# io-board-f-2.net
KiCad netlist of a schematic drawn in EAGLE
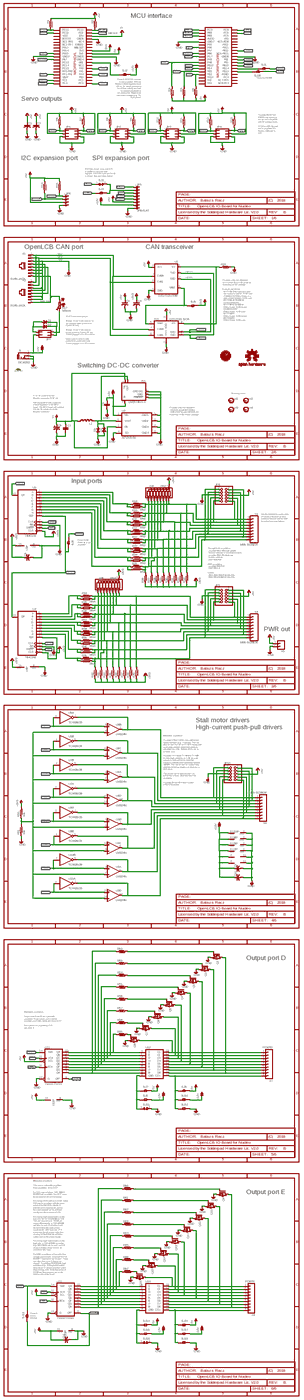
[diagram p0: schematic, sheet 1, overview]
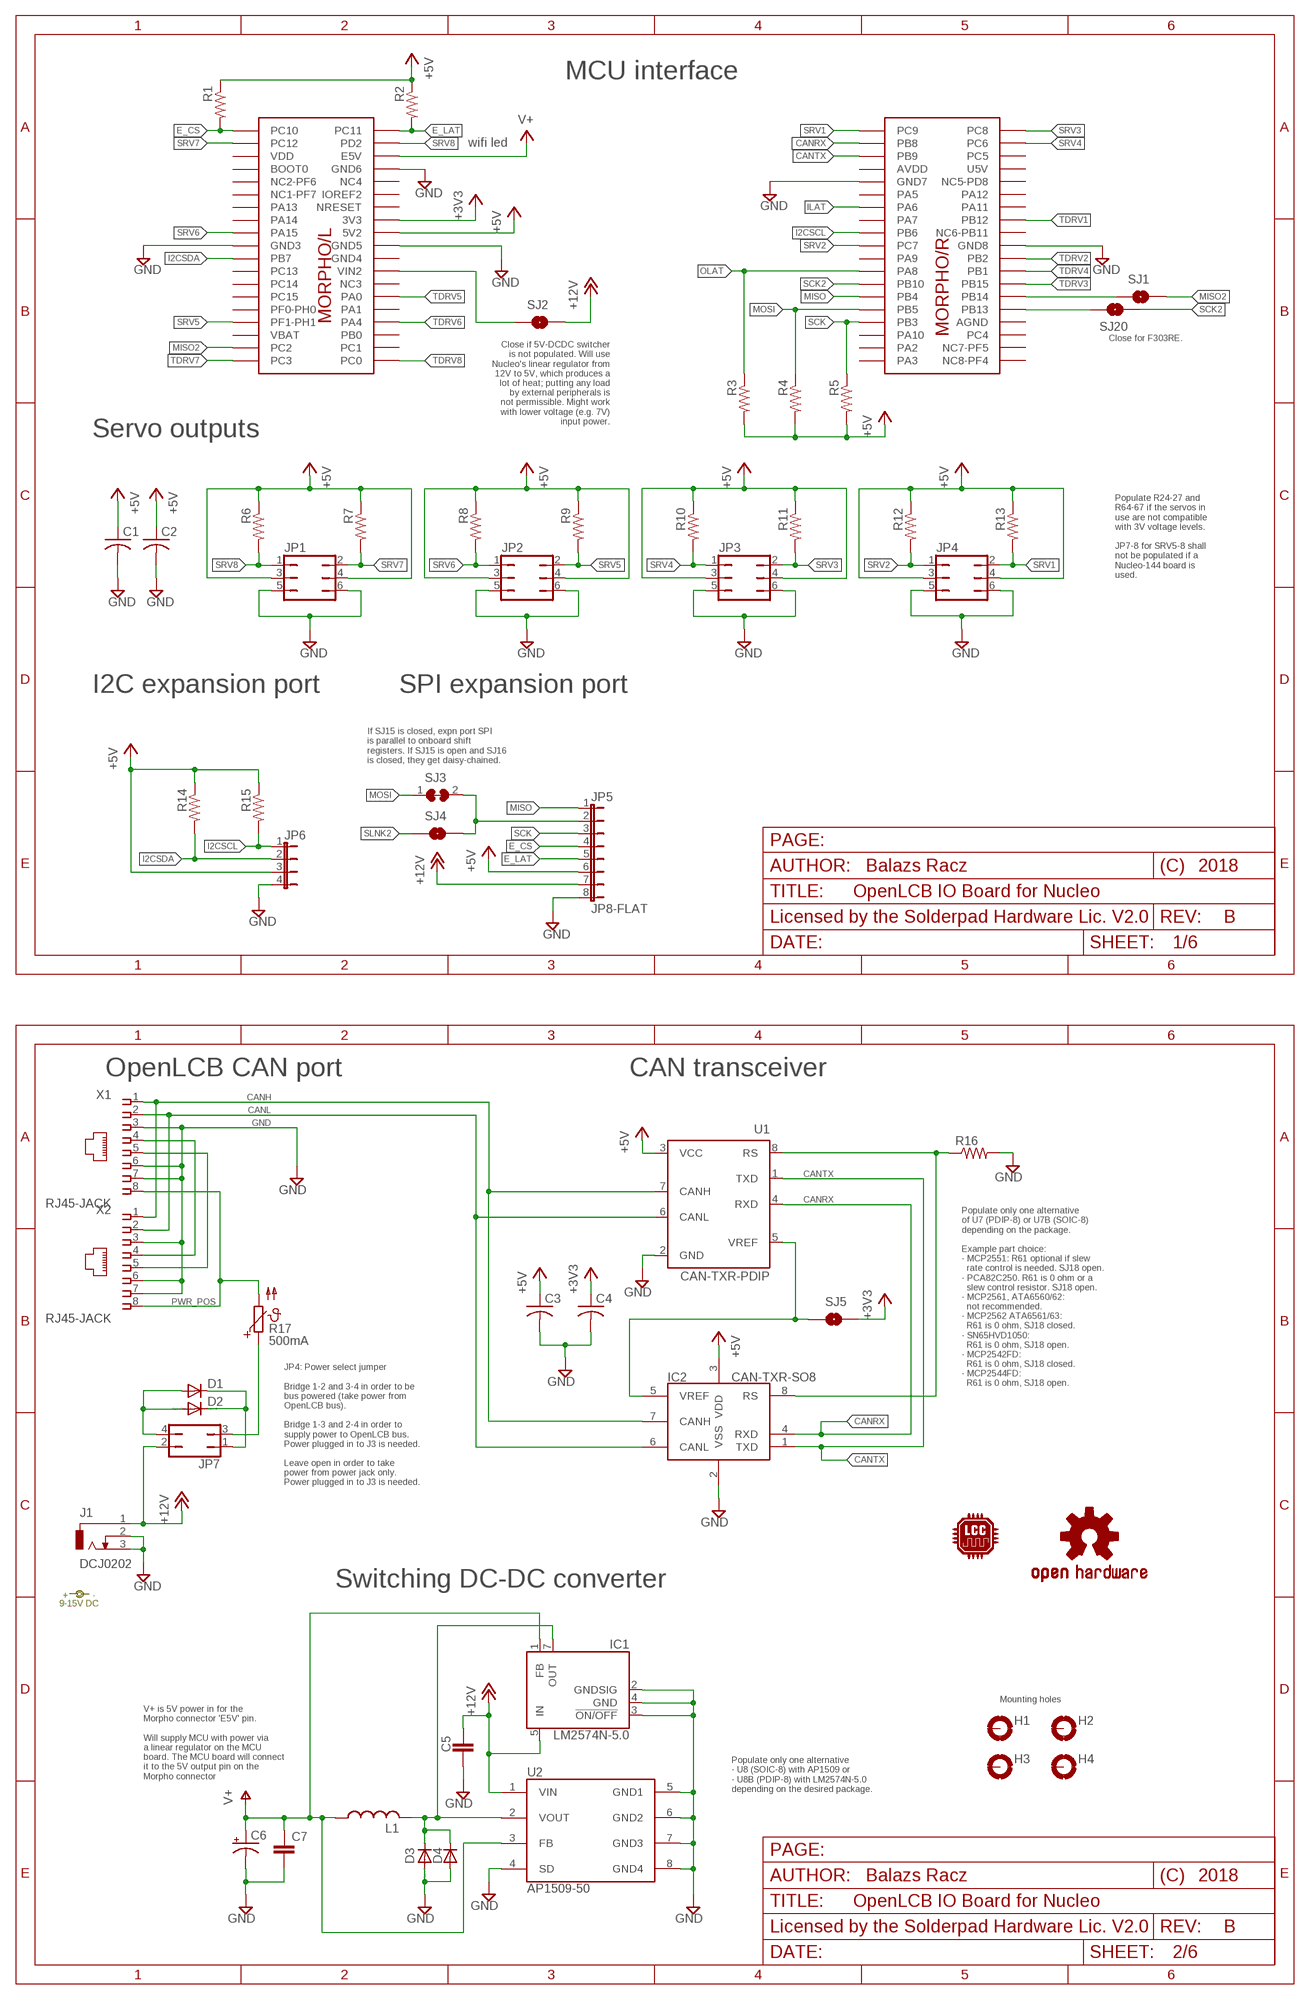
[diagram p1: schematic, sheet 1, part 1 of 4]
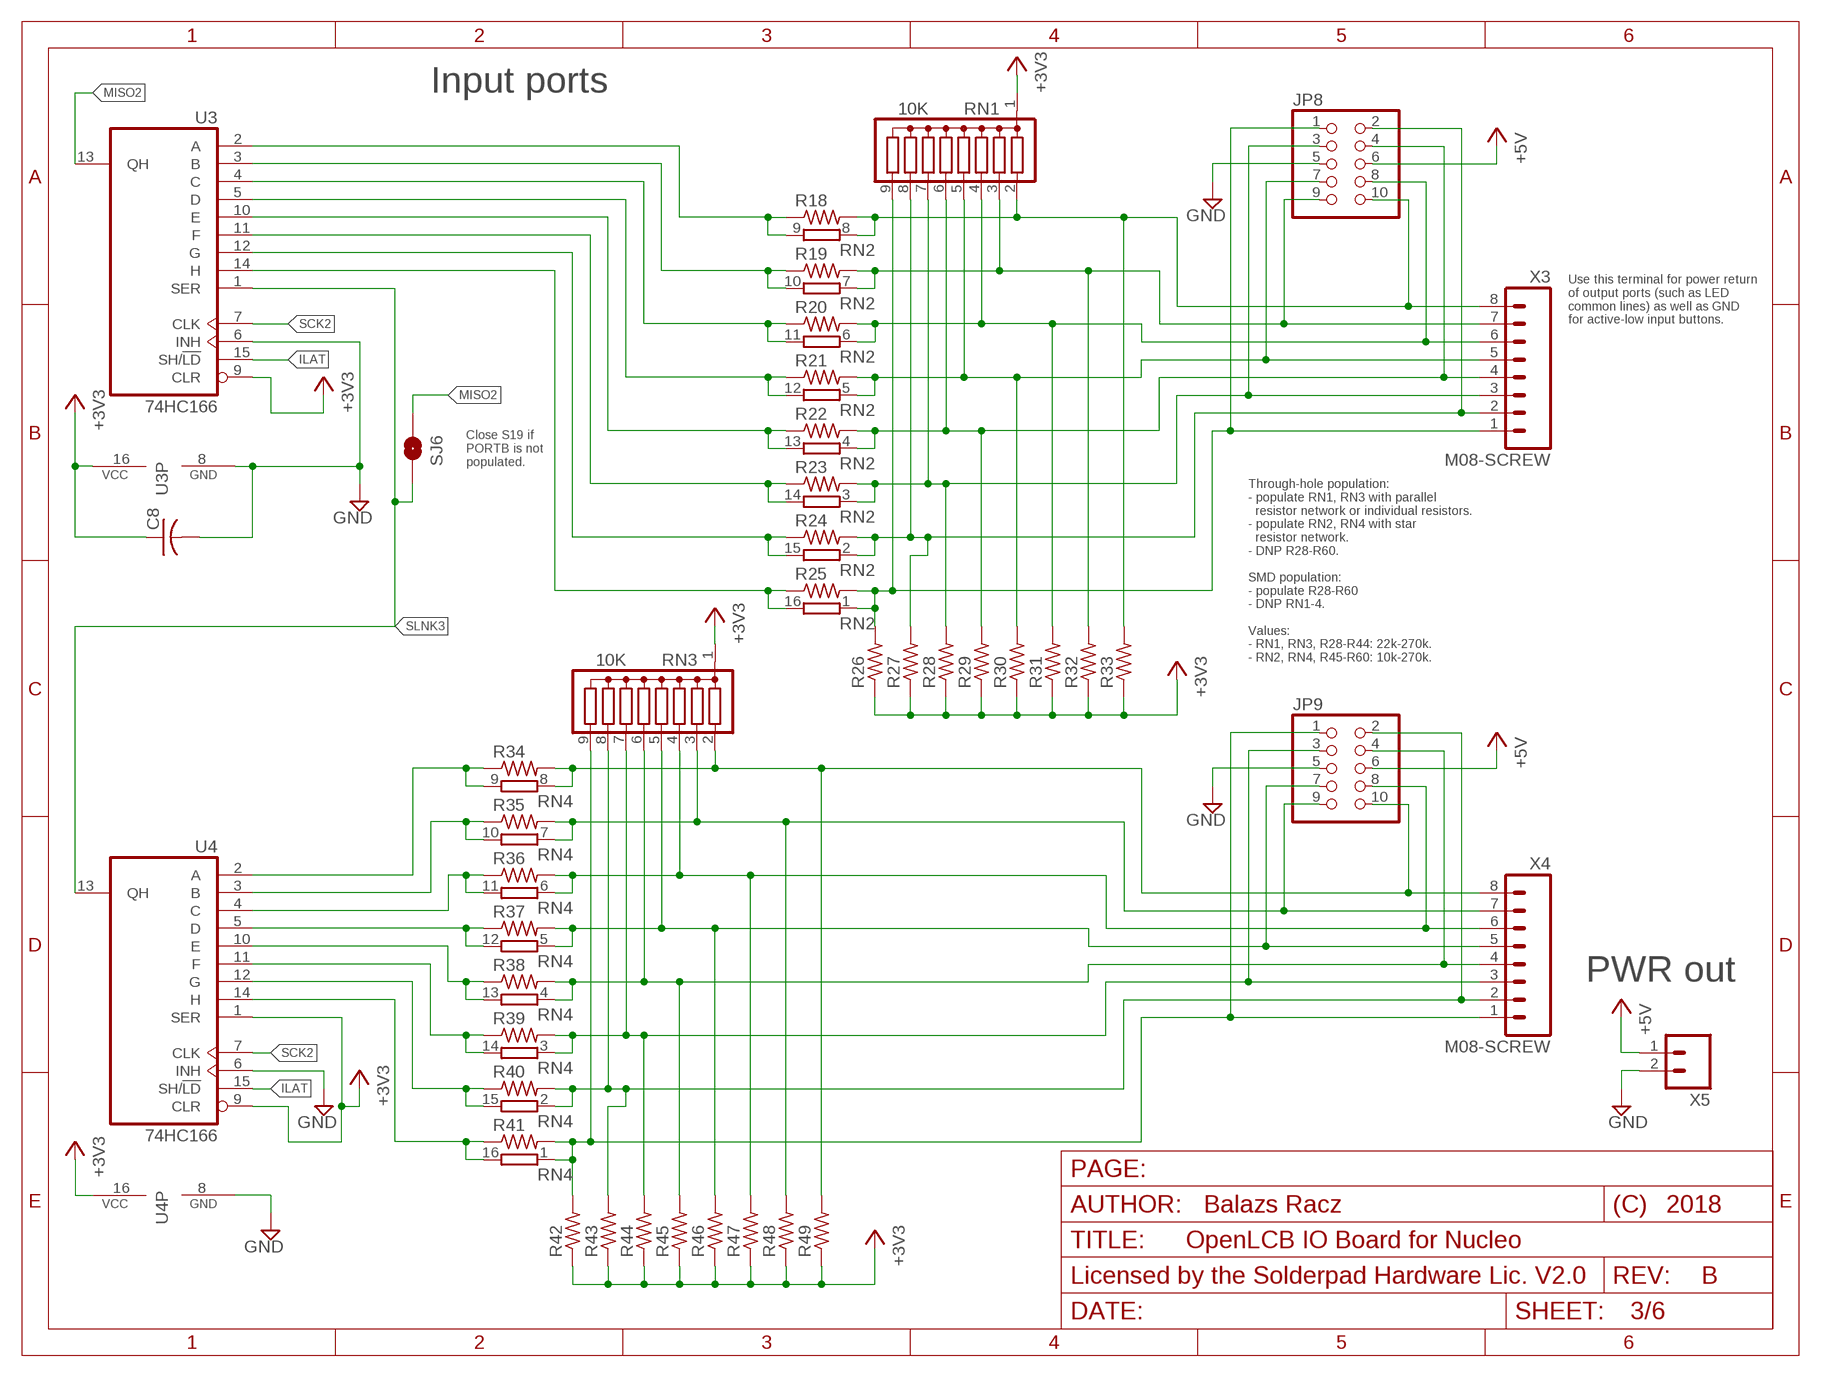
[diagram p2: schematic, sheet 1, part 2 of 4]
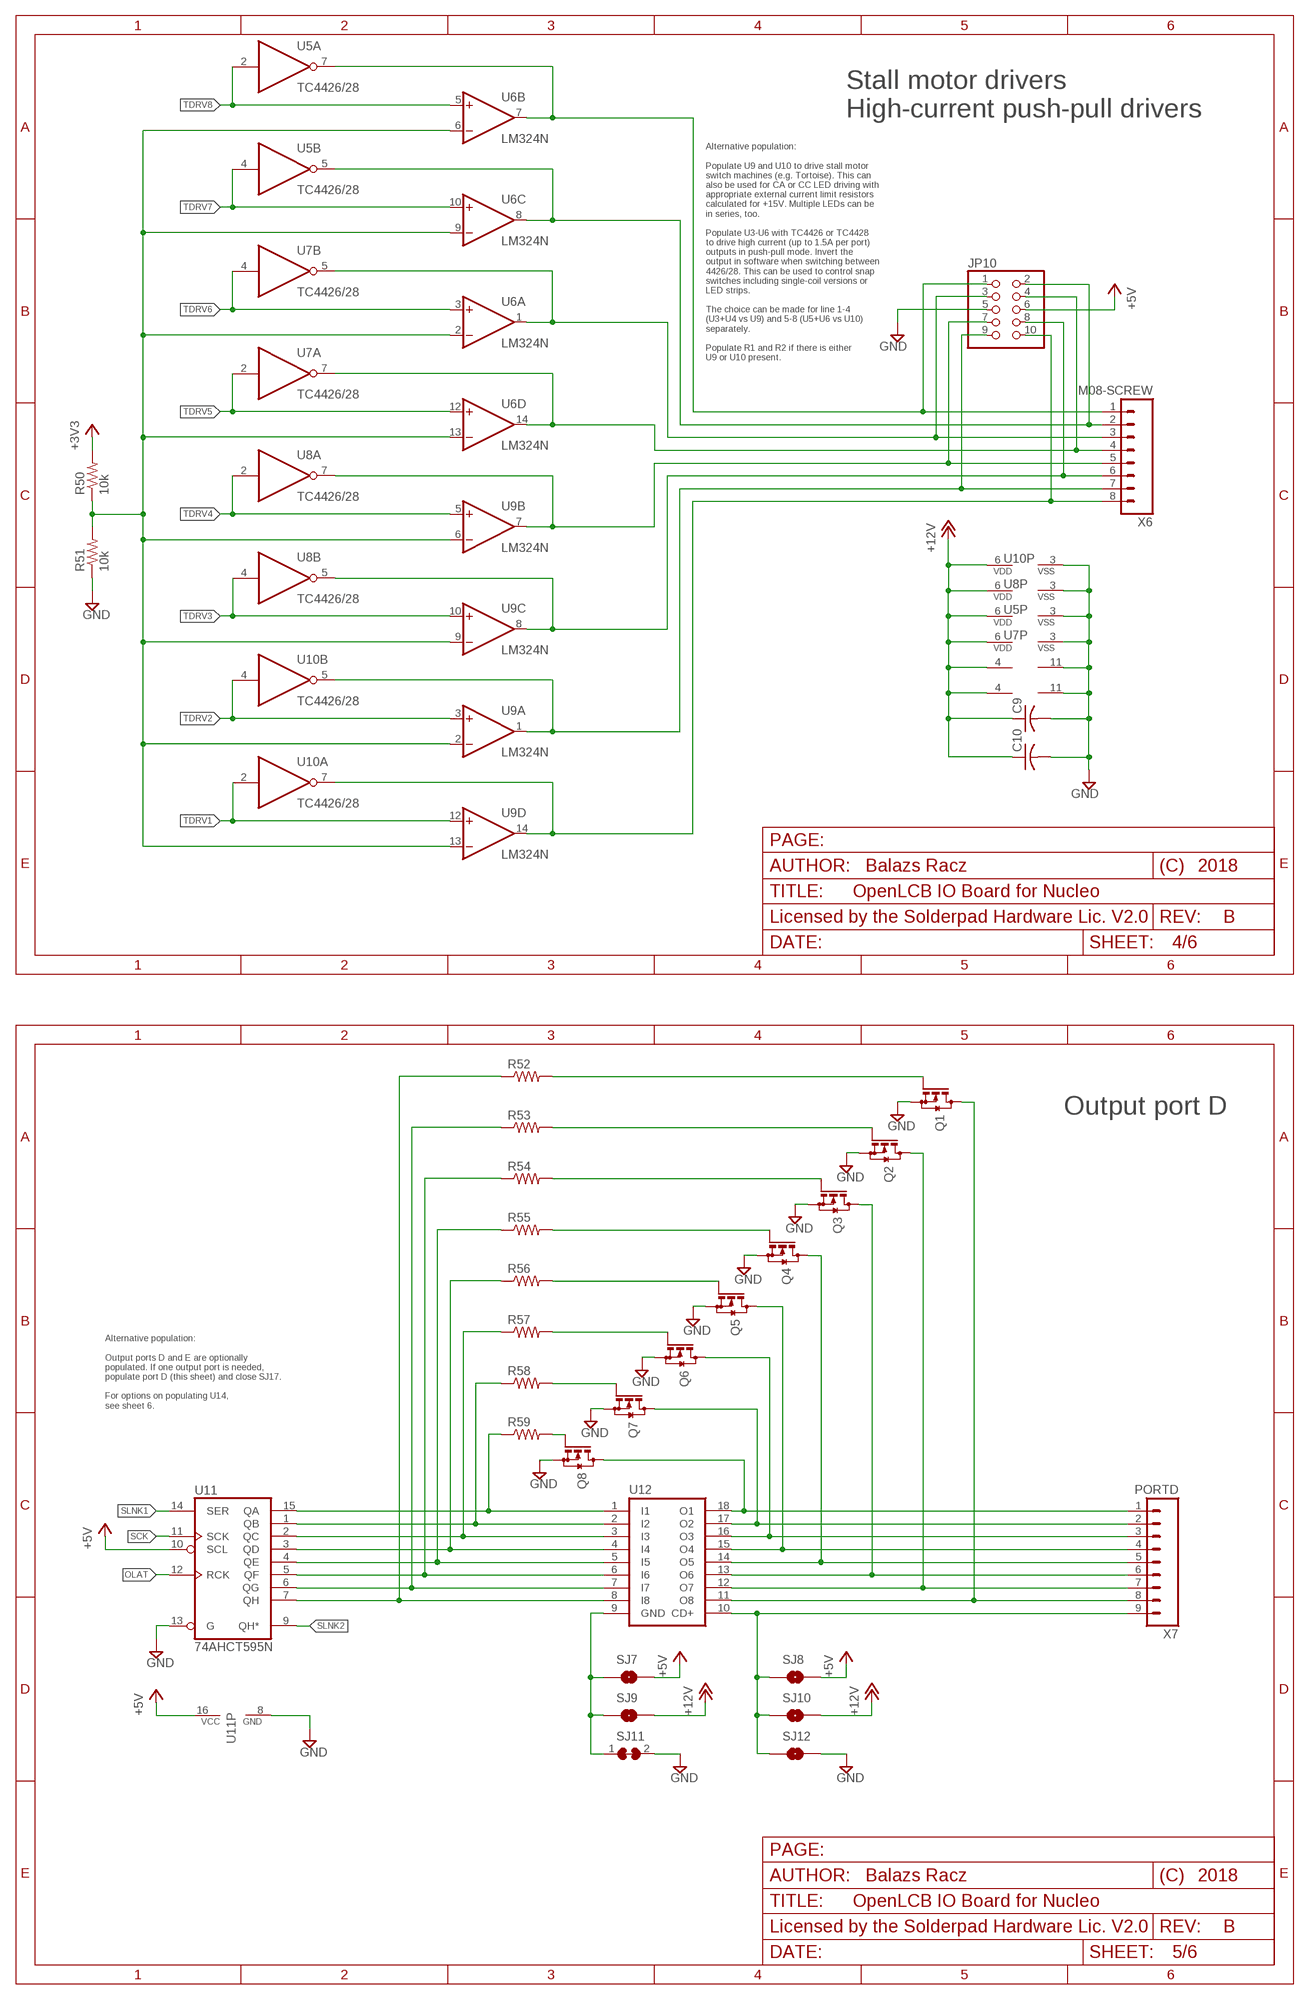
[diagram p3: schematic, sheet 1, part 3 of 4]
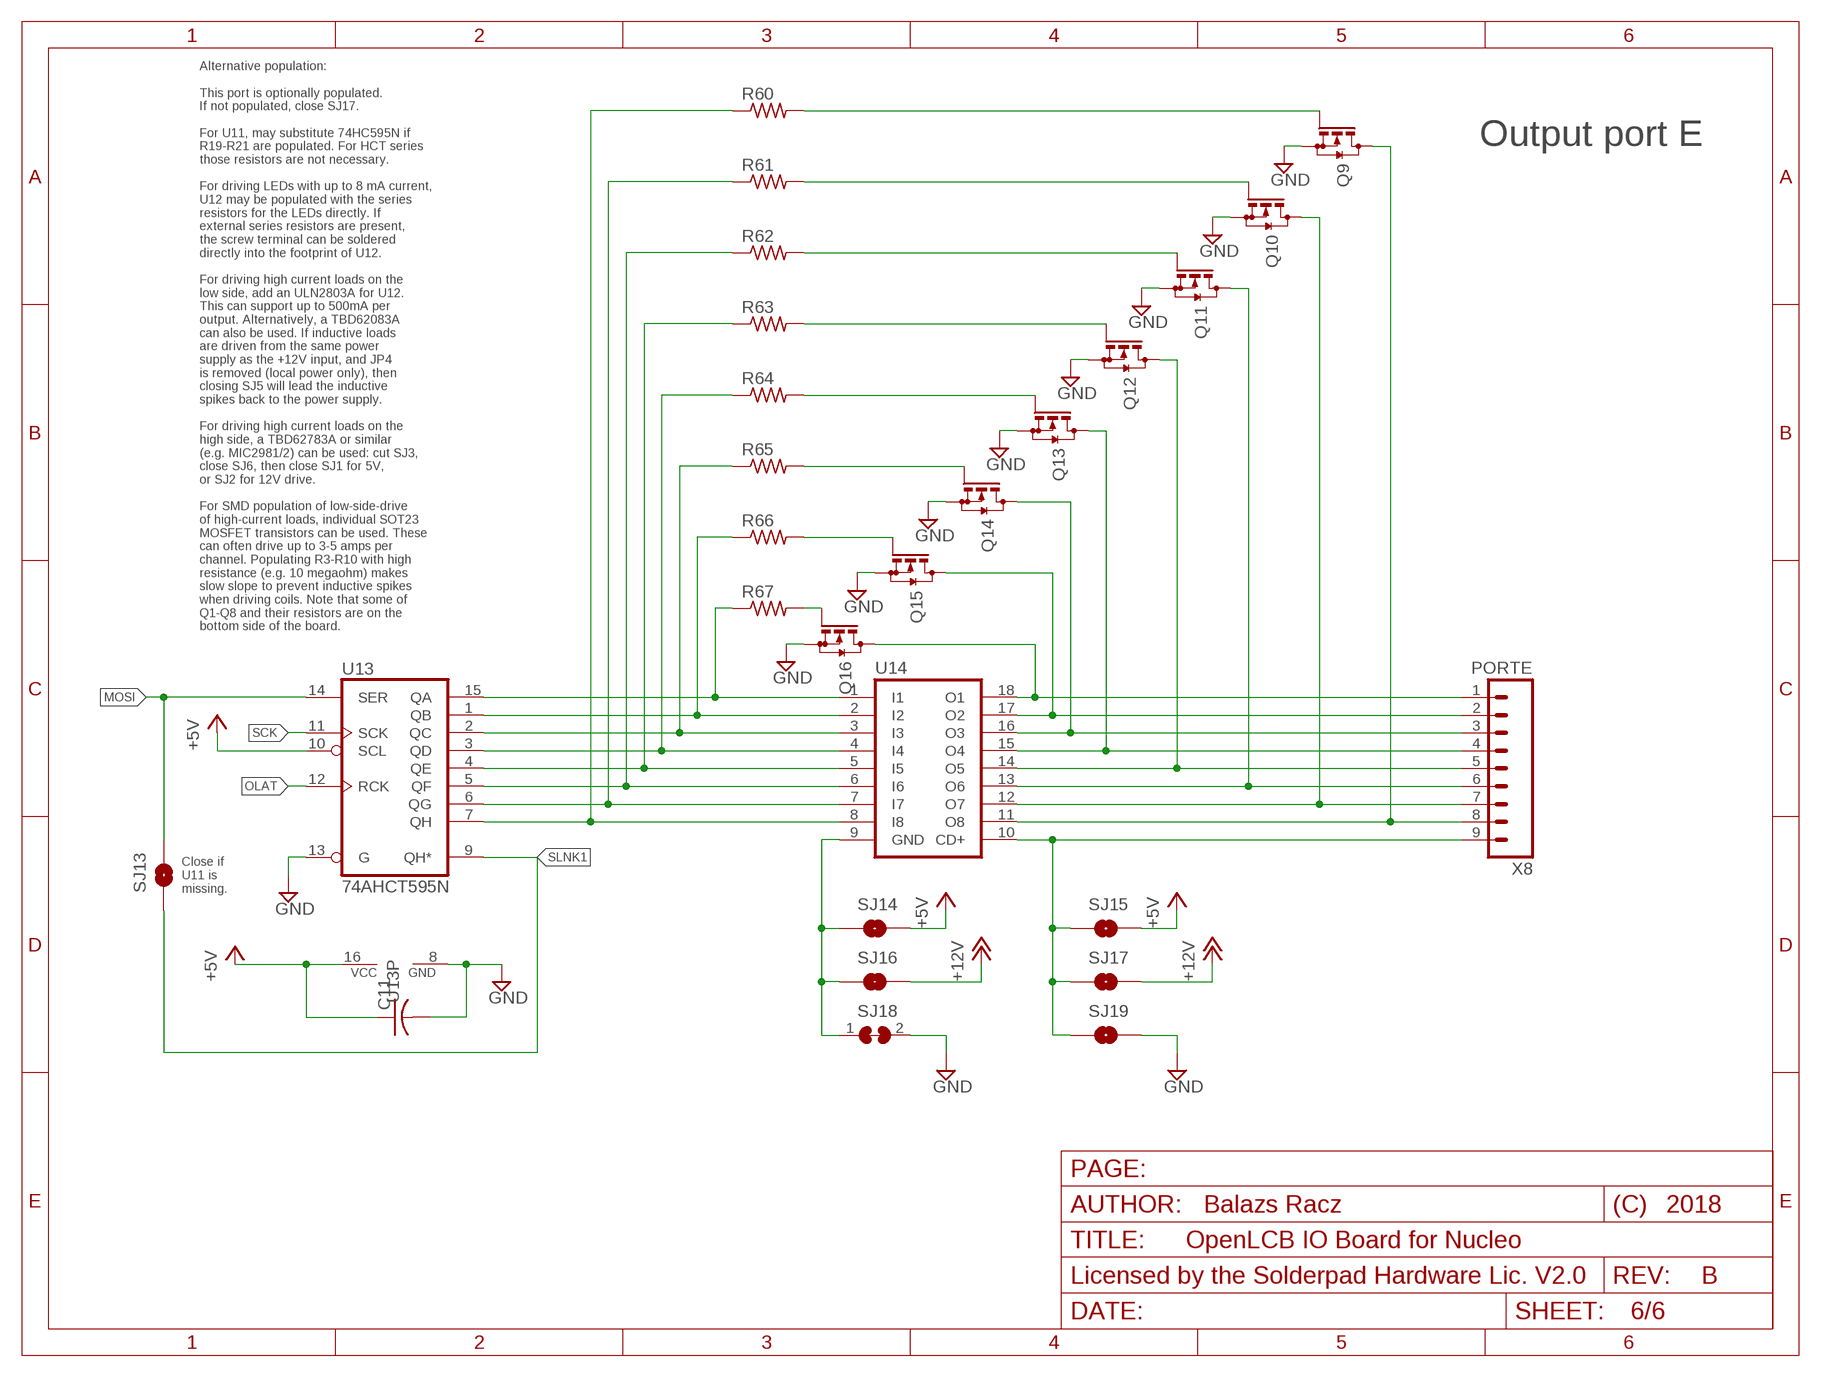
[diagram p4: schematic, sheet 1, part 4 of 4]

(export (version "E")
  (design (tool "Eeschema 10.0.6"))
  (components
    (comp (ref "C1")
      (value "C-USC1206")
      (footprint "eagle-import:C1206")
      (libsource (lib "eagle-import") (part "C-USC1206"))
    )
    (comp (ref "C2")
      (value "C-USC1206")
      (footprint "eagle-import:C1206")
      (libsource (lib "eagle-import") (part "C-USC1206"))
    )
    (comp (ref "C3")
      (value "C-USC0805")
      (footprint "eagle-import:C0805")
      (libsource (lib "eagle-import") (part "C-USC0805"))
    )
    (comp (ref "C4")
      (value "C-USC0805")
      (footprint "eagle-import:C0805")
      (libsource (lib "eagle-import") (part "C-USC0805"))
    )
    (comp (ref "C5")
      (value "C-EUC1206")
      (footprint "eagle-import:C1206")
      (libsource (lib "eagle-import") (part "C-EUC1206"))
    )
    (comp (ref "C6")
      (value "CPOL-USE2.5-5")
      (footprint "eagle-import:E2,5-5")
      (libsource (lib "eagle-import") (part "CPOL-USE2.5-5"))
    )
    (comp (ref "C7")
      (value "C-EUC1206")
      (footprint "eagle-import:C1206")
      (libsource (lib "eagle-import") (part "C-EUC1206"))
    )
    (comp (ref "C8")
      (value "C-USC0805")
      (footprint "eagle-import:C0805")
      (libsource (lib "eagle-import") (part "C-USC0805"))
    )
    (comp (ref "C9")
      (value "C-USC1206")
      (footprint "eagle-import:C1206")
      (libsource (lib "eagle-import") (part "C-USC1206"))
    )
    (comp (ref "C10")
      (value "C-USC1206")
      (footprint "eagle-import:C1206")
      (libsource (lib "eagle-import") (part "C-USC1206"))
    )
    (comp (ref "C11")
      (value "C-USC0805")
      (footprint "eagle-import:C0805")
      (libsource (lib "eagle-import") (part "C-USC0805"))
    )
    (comp (ref "D1")
      (value "DIODEDO-214AA-NODOC")
      (footprint "eagle-import:DO214AA-NODOC")
      (libsource (lib "eagle-import") (part "DIODEDO-214AA-NODOC"))
    )
    (comp (ref "D2")
      (value "DIODE-DO41-7.6")
      (footprint "eagle-import:DO41-7.6")
      (libsource (lib "eagle-import") (part "DIODE-DO41-7.6"))
    )
    (comp (ref "D3")
      (value "DIODE-DO41-7.6")
      (footprint "eagle-import:DO41-7.6")
      (libsource (lib "eagle-import") (part "DIODE-DO41-7.6"))
    )
    (comp (ref "D4")
      (value "DIODEDO-214AA-NODOC")
      (footprint "eagle-import:DO214AA-NODOC")
      (libsource (lib "eagle-import") (part "DIODEDO-214AA-NODOC"))
    )
    (comp (ref "G1")
      (value "NUCLEO_64_GENERIC")
      (footprint "eagle-import:NUCLEO_BRD_BASE64")
      (libsource (lib "eagle-import") (part "NUCLEO_64_GENERIC"))
    )
    (comp (ref "H1")
      (value "MOUNT-PAD-ROUND3.3")
      (footprint "eagle-import:3,3-PAD")
      (libsource (lib "eagle-import") (part "MOUNT-PAD-ROUND3.3"))
    )
    (comp (ref "H2")
      (value "MOUNT-PAD-ROUND3.3")
      (footprint "eagle-import:3,3-PAD")
      (libsource (lib "eagle-import") (part "MOUNT-PAD-ROUND3.3"))
    )
    (comp (ref "H3")
      (value "MOUNT-PAD-ROUND3.3")
      (footprint "eagle-import:3,3-PAD")
      (libsource (lib "eagle-import") (part "MOUNT-PAD-ROUND3.3"))
    )
    (comp (ref "H4")
      (value "MOUNT-PAD-ROUND3.3")
      (footprint "eagle-import:3,3-PAD")
      (libsource (lib "eagle-import") (part "MOUNT-PAD-ROUND3.3"))
    )
    (comp (ref "IC1")
      (value "LM2574N-5.0")
      (footprint "eagle-import:DIL08")
      (libsource (lib "eagle-import") (part "LM2574?-N5.0"))
    )
    (comp (ref "IC2")
      (value "CAN-TXR-SO8")
      (footprint "eagle-import:SO-08")
      (libsource (lib "eagle-import") (part "MCP2551-SN"))
    )
    (comp (ref "J1")
      (value "DCJ0202")
      (footprint "eagle-import:DCJ0202")
      (libsource (lib "eagle-import") (part "DCJ0202"))
    )
    (comp (ref "JP1")
      (value "JP3Q")
      (footprint "eagle-import:JP3Q")
      (libsource (lib "eagle-import") (part "JP3Q"))
    )
    (comp (ref "JP2")
      (value "JP3Q")
      (footprint "eagle-import:JP3Q")
      (libsource (lib "eagle-import") (part "JP3Q"))
    )
    (comp (ref "JP3")
      (value "JP3Q")
      (footprint "eagle-import:JP3Q")
      (libsource (lib "eagle-import") (part "JP3Q"))
    )
    (comp (ref "JP4")
      (value "JP3Q")
      (footprint "eagle-import:JP3Q")
      (libsource (lib "eagle-import") (part "JP3Q"))
    )
    (comp (ref "JP5")
      (value "JP8-FLAT")
      (footprint "eagle-import:JP8F")
      (libsource (lib "eagle-import") (part "JP8-FLAT"))
    )
    (comp (ref "JP6")
      (value "JP4-FLAT")
      (footprint "eagle-import:JP4F")
      (libsource (lib "eagle-import") (part "JP4-FLAT"))
    )
    (comp (ref "JP7")
      (value "JP2Q")
      (footprint "eagle-import:JP2Q")
      (libsource (lib "eagle-import") (part "JP2Q"))
    )
    (comp (ref "JP8")
      (value "PINHD-2X5CN")
      (footprint "eagle-import:CON10M")
      (libsource (lib "eagle-import") (part "PINHD-2X5CN"))
    )
    (comp (ref "JP9")
      (value "PINHD-2X5CN")
      (footprint "eagle-import:CON10M")
      (libsource (lib "eagle-import") (part "PINHD-2X5CN"))
    )
    (comp (ref "JP10")
      (value "PINHD-2X5CN")
      (footprint "eagle-import:CON10M")
      (libsource (lib "eagle-import") (part "PINHD-2X5CN"))
    )
    (comp (ref "L1")
      (value "L-US")
      (footprint "eagle-import:L5-8,5")
      (libsource (lib "eagle-import") (part "L-US"))
    )
    (comp (ref "LG1")
      (value "LCC_LOGO")
      (footprint "eagle-import:LCC_LOGO")
      (libsource (lib "eagle-import") (part "LCC_LOGO"))
    )
    (comp (ref "LOGO1")
      (value "DOC-OSHW-LOGOM")
      (footprint "eagle-import:OSHW-LOGO-M")
      (libsource (lib "eagle-import") (part "DOC-OSHW-LOGOM"))
    )
    (comp (ref "P1")
      (value "9-15V DC")
      (footprint "eagle-import:POWER_USAGE")
      (libsource (lib "eagle-import") (part "DOC-POWER_LABEL"))
    )
    (comp (ref "Q1")
      (value "BSS123")
      (footprint "eagle-import:SOT23")
      (libsource (lib "eagle-import") (part "BSS123"))
    )
    (comp (ref "Q2")
      (value "BSS123")
      (footprint "eagle-import:SOT23")
      (libsource (lib "eagle-import") (part "BSS123"))
    )
    (comp (ref "Q3")
      (value "BSS123")
      (footprint "eagle-import:SOT23")
      (libsource (lib "eagle-import") (part "BSS123"))
    )
    (comp (ref "Q4")
      (value "BSS123")
      (footprint "eagle-import:SOT23")
      (libsource (lib "eagle-import") (part "BSS123"))
    )
    (comp (ref "Q5")
      (value "BSS123")
      (footprint "eagle-import:SOT23")
      (libsource (lib "eagle-import") (part "BSS123"))
    )
    (comp (ref "Q6")
      (value "BSS123")
      (footprint "eagle-import:SOT23")
      (libsource (lib "eagle-import") (part "BSS123"))
    )
    (comp (ref "Q7")
      (value "BSS123")
      (footprint "eagle-import:SOT23")
      (libsource (lib "eagle-import") (part "BSS123"))
    )
    (comp (ref "Q8")
      (value "BSS123")
      (footprint "eagle-import:SOT23")
      (libsource (lib "eagle-import") (part "BSS123"))
    )
    (comp (ref "Q9")
      (value "BSS123")
      (footprint "eagle-import:SOT23")
      (libsource (lib "eagle-import") (part "BSS123"))
    )
    (comp (ref "Q10")
      (value "BSS123")
      (footprint "eagle-import:SOT23")
      (libsource (lib "eagle-import") (part "BSS123"))
    )
    (comp (ref "Q11")
      (value "BSS123")
      (footprint "eagle-import:SOT23")
      (libsource (lib "eagle-import") (part "BSS123"))
    )
    (comp (ref "Q12")
      (value "BSS123")
      (footprint "eagle-import:SOT23")
      (libsource (lib "eagle-import") (part "BSS123"))
    )
    (comp (ref "Q13")
      (value "BSS123")
      (footprint "eagle-import:SOT23")
      (libsource (lib "eagle-import") (part "BSS123"))
    )
    (comp (ref "Q14")
      (value "BSS123")
      (footprint "eagle-import:SOT23")
      (libsource (lib "eagle-import") (part "BSS123"))
    )
    (comp (ref "Q15")
      (value "BSS123")
      (footprint "eagle-import:SOT23")
      (libsource (lib "eagle-import") (part "BSS123"))
    )
    (comp (ref "Q16")
      (value "BSS123")
      (footprint "eagle-import:SOT23")
      (libsource (lib "eagle-import") (part "BSS123"))
    )
    (comp (ref "R1")
      (value "R-US_R0805")
      (footprint "eagle-import:R0805")
      (libsource (lib "eagle-import") (part "rcl_334_R-US_R0805"))
    )
    (comp (ref "R2")
      (value "R-US_R0805")
      (footprint "eagle-import:R0805")
      (libsource (lib "eagle-import") (part "rcl_334_R-US_R0805"))
    )
    (comp (ref "R3")
      (value "R-US_R0805")
      (footprint "eagle-import:R0805")
      (libsource (lib "eagle-import") (part "rcl_334_R-US_R0805"))
    )
    (comp (ref "R4")
      (value "R-US_R0805")
      (footprint "eagle-import:R0805")
      (libsource (lib "eagle-import") (part "rcl_334_R-US_R0805"))
    )
    (comp (ref "R5")
      (value "R-US_R0805")
      (footprint "eagle-import:R0805")
      (libsource (lib "eagle-import") (part "rcl_334_R-US_R0805"))
    )
    (comp (ref "R6")
      (value "R-US_R0805")
      (footprint "eagle-import:R0805")
      (libsource (lib "eagle-import") (part "rcl_334_R-US_R0805"))
    )
    (comp (ref "R7")
      (value "R-US_R0805")
      (footprint "eagle-import:R0805")
      (libsource (lib "eagle-import") (part "rcl_334_R-US_R0805"))
    )
    (comp (ref "R8")
      (value "R-US_R0805")
      (footprint "eagle-import:R0805")
      (libsource (lib "eagle-import") (part "rcl_334_R-US_R0805"))
    )
    (comp (ref "R9")
      (value "R-US_R0805")
      (footprint "eagle-import:R0805")
      (libsource (lib "eagle-import") (part "rcl_334_R-US_R0805"))
    )
    (comp (ref "R10")
      (value "R-US_R0805")
      (footprint "eagle-import:R0805")
      (libsource (lib "eagle-import") (part "rcl_334_R-US_R0805"))
    )
    (comp (ref "R11")
      (value "R-US_R0805")
      (footprint "eagle-import:R0805")
      (libsource (lib "eagle-import") (part "rcl_334_R-US_R0805"))
    )
    (comp (ref "R12")
      (value "R-US_R0805")
      (footprint "eagle-import:R0805")
      (libsource (lib "eagle-import") (part "rcl_334_R-US_R0805"))
    )
    (comp (ref "R13")
      (value "R-US_R0805")
      (footprint "eagle-import:R0805")
      (libsource (lib "eagle-import") (part "rcl_334_R-US_R0805"))
    )
    (comp (ref "R14")
      (value "R-US_R0805")
      (footprint "eagle-import:R0805")
      (libsource (lib "eagle-import") (part "rcl_334_R-US_R0805"))
    )
    (comp (ref "R15")
      (value "R-US_R0805")
      (footprint "eagle-import:R0805")
      (libsource (lib "eagle-import") (part "rcl_334_R-US_R0805"))
    )
    (comp (ref "R16")
      (value "R-US_R0805")
      (footprint "eagle-import:R0805")
      (libsource (lib "eagle-import") (part "rcl_334_R-US_R0805"))
    )
    (comp (ref "R17")
      (value "500mA")
      (footprint "eagle-import:PTC1812")
      (libsource (lib "eagle-import") (part "PTC_1812"))
    )
    (comp (ref "R18")
      (value "R-US_R0603")
      (footprint "eagle-import:R0603")
      (libsource (lib "eagle-import") (part "rcl_334_R-US_R0603"))
    )
    (comp (ref "R19")
      (value "R-US_R0603")
      (footprint "eagle-import:R0603")
      (libsource (lib "eagle-import") (part "rcl_334_R-US_R0603"))
    )
    (comp (ref "R20")
      (value "R-US_R0603")
      (footprint "eagle-import:R0603")
      (libsource (lib "eagle-import") (part "rcl_334_R-US_R0603"))
    )
    (comp (ref "R21")
      (value "R-US_R0603")
      (footprint "eagle-import:R0603")
      (libsource (lib "eagle-import") (part "rcl_334_R-US_R0603"))
    )
    (comp (ref "R22")
      (value "R-US_R0603")
      (footprint "eagle-import:R0603")
      (libsource (lib "eagle-import") (part "rcl_334_R-US_R0603"))
    )
    (comp (ref "R23")
      (value "R-US_R0603")
      (footprint "eagle-import:R0603")
      (libsource (lib "eagle-import") (part "rcl_334_R-US_R0603"))
    )
    (comp (ref "R24")
      (value "R-US_R0603")
      (footprint "eagle-import:R0603")
      (libsource (lib "eagle-import") (part "rcl_334_R-US_R0603"))
    )
    (comp (ref "R25")
      (value "R-US_R0603")
      (footprint "eagle-import:R0603")
      (libsource (lib "eagle-import") (part "rcl_334_R-US_R0603"))
    )
    (comp (ref "R26")
      (value "R-US")
      (footprint "eagle-import:R0603")
      (libsource (lib "eagle-import") (part "R-US"))
    )
    (comp (ref "R27")
      (value "R-US")
      (footprint "eagle-import:R0603")
      (libsource (lib "eagle-import") (part "R-US"))
    )
    (comp (ref "R28")
      (value "R-US")
      (footprint "eagle-import:R0603")
      (libsource (lib "eagle-import") (part "R-US"))
    )
    (comp (ref "R29")
      (value "R-US")
      (footprint "eagle-import:R0603")
      (libsource (lib "eagle-import") (part "R-US"))
    )
    (comp (ref "R30")
      (value "R-US")
      (footprint "eagle-import:R0603")
      (libsource (lib "eagle-import") (part "R-US"))
    )
    (comp (ref "R31")
      (value "R-US")
      (footprint "eagle-import:R0603")
      (libsource (lib "eagle-import") (part "R-US"))
    )
    (comp (ref "R32")
      (value "R-US")
      (footprint "eagle-import:R0603")
      (libsource (lib "eagle-import") (part "R-US"))
    )
    (comp (ref "R33")
      (value "R-US")
      (footprint "eagle-import:R0603")
      (libsource (lib "eagle-import") (part "R-US"))
    )
    (comp (ref "R34")
      (value "R-US_R0603")
      (footprint "eagle-import:R0603")
      (libsource (lib "eagle-import") (part "rcl_334_R-US_R0603"))
    )
    (comp (ref "R35")
      (value "R-US_R0603")
      (footprint "eagle-import:R0603")
      (libsource (lib "eagle-import") (part "rcl_334_R-US_R0603"))
    )
    (comp (ref "R36")
      (value "R-US_R0603")
      (footprint "eagle-import:R0603")
      (libsource (lib "eagle-import") (part "rcl_334_R-US_R0603"))
    )
    (comp (ref "R37")
      (value "R-US_R0603")
      (footprint "eagle-import:R0603")
      (libsource (lib "eagle-import") (part "rcl_334_R-US_R0603"))
    )
    (comp (ref "R38")
      (value "R-US_R0603")
      (footprint "eagle-import:R0603")
      (libsource (lib "eagle-import") (part "rcl_334_R-US_R0603"))
    )
    (comp (ref "R39")
      (value "R-US_R0603")
      (footprint "eagle-import:R0603")
      (libsource (lib "eagle-import") (part "rcl_334_R-US_R0603"))
    )
    (comp (ref "R40")
      (value "R-US_R0603")
      (footprint "eagle-import:R0603")
      (libsource (lib "eagle-import") (part "rcl_334_R-US_R0603"))
    )
    (comp (ref "R41")
      (value "R-US_R0603")
      (footprint "eagle-import:R0603")
      (libsource (lib "eagle-import") (part "rcl_334_R-US_R0603"))
    )
    (comp (ref "R42")
      (value "R-US")
      (footprint "eagle-import:R0603")
      (libsource (lib "eagle-import") (part "R-US"))
    )
    (comp (ref "R43")
      (value "R-US")
      (footprint "eagle-import:R0603")
      (libsource (lib "eagle-import") (part "R-US"))
    )
    (comp (ref "R44")
      (value "R-US")
      (footprint "eagle-import:R0603")
      (libsource (lib "eagle-import") (part "R-US"))
    )
    (comp (ref "R45")
      (value "R-US")
      (footprint "eagle-import:R0603")
      (libsource (lib "eagle-import") (part "R-US"))
    )
    (comp (ref "R46")
      (value "R-US")
      (footprint "eagle-import:R0603")
      (libsource (lib "eagle-import") (part "R-US"))
    )
    (comp (ref "R47")
      (value "R-US")
      (footprint "eagle-import:R0603")
      (libsource (lib "eagle-import") (part "R-US"))
    )
    (comp (ref "R48")
      (value "R-US")
      (footprint "eagle-import:R0603")
      (libsource (lib "eagle-import") (part "R-US"))
    )
    (comp (ref "R49")
      (value "R-US")
      (footprint "eagle-import:R0603")
      (libsource (lib "eagle-import") (part "R-US"))
    )
    (comp (ref "R50")
      (value "10k")
      (footprint "eagle-import:R0805")
      (libsource (lib "eagle-import") (part "R-US_R0805"))
    )
    (comp (ref "R51")
      (value "10k")
      (footprint "eagle-import:R0805")
      (libsource (lib "eagle-import") (part "R-US_R0805"))
    )
    (comp (ref "R52")
      (value "R-US_R0603")
      (footprint "eagle-import:R0603")
      (libsource (lib "eagle-import") (part "R-US_R0603"))
    )
    (comp (ref "R53")
      (value "R-US_R0603")
      (footprint "eagle-import:R0603")
      (libsource (lib "eagle-import") (part "R-US_R0603"))
    )
    (comp (ref "R54")
      (value "R-US_R0603")
      (footprint "eagle-import:R0603")
      (libsource (lib "eagle-import") (part "R-US_R0603"))
    )
    (comp (ref "R55")
      (value "R-US_R0603")
      (footprint "eagle-import:R0603")
      (libsource (lib "eagle-import") (part "R-US_R0603"))
    )
    (comp (ref "R56")
      (value "R-US_R0603")
      (footprint "eagle-import:R0603")
      (libsource (lib "eagle-import") (part "R-US_R0603"))
    )
    (comp (ref "R57")
      (value "R-US_R0603")
      (footprint "eagle-import:R0603")
      (libsource (lib "eagle-import") (part "R-US_R0603"))
    )
    (comp (ref "R58")
      (value "R-US_R0603")
      (footprint "eagle-import:R0603")
      (libsource (lib "eagle-import") (part "R-US_R0603"))
    )
    (comp (ref "R59")
      (value "R-US_R0603")
      (footprint "eagle-import:R0603")
      (libsource (lib "eagle-import") (part "R-US_R0603"))
    )
    (comp (ref "R60")
      (value "R-US_R0603")
      (footprint "eagle-import:R0603")
      (libsource (lib "eagle-import") (part "R-US_R0603"))
    )
    (comp (ref "R61")
      (value "R-US_R0603")
      (footprint "eagle-import:R0603")
      (libsource (lib "eagle-import") (part "R-US_R0603"))
    )
    (comp (ref "R62")
      (value "R-US_R0603")
      (footprint "eagle-import:R0603")
      (libsource (lib "eagle-import") (part "R-US_R0603"))
    )
    (comp (ref "R63")
      (value "R-US_R0603")
      (footprint "eagle-import:R0603")
      (libsource (lib "eagle-import") (part "R-US_R0603"))
    )
    (comp (ref "R64")
      (value "R-US_R0603")
      (footprint "eagle-import:R0603")
      (libsource (lib "eagle-import") (part "R-US_R0603"))
    )
    (comp (ref "R65")
      (value "R-US_R0603")
      (footprint "eagle-import:R0603")
      (libsource (lib "eagle-import") (part "R-US_R0603"))
    )
    (comp (ref "R66")
      (value "R-US_R0603")
      (footprint "eagle-import:R0603")
      (libsource (lib "eagle-import") (part "R-US_R0603"))
    )
    (comp (ref "R67")
      (value "R-US_R0603")
      (footprint "eagle-import:R0603")
      (libsource (lib "eagle-import") (part "R-US_R0603"))
    )
    (comp (ref "RN1")
      (value "10K")
      (footprint "eagle-import:SIL9")
      (libsource (lib "eagle-import") (part "G08R"))
    )
    (comp (ref "RN2")
      (value "8R-P")
      (footprint "eagle-import:DIL16")
      (libsource (lib "eagle-import") (part "8R-P"))
    )
    (comp (ref "RN3")
      (value "10K")
      (footprint "eagle-import:SIL9")
      (libsource (lib "eagle-import") (part "G08R"))
    )
    (comp (ref "RN4")
      (value "8R-P")
      (footprint "eagle-import:DIL16")
      (libsource (lib "eagle-import") (part "8R-P"))
    )
    (comp (ref "SJ1")
      (value "SJRND2")
      (footprint "eagle-import:SJ_RND2")
      (libsource (lib "eagle-import") (part "SJRND2"))
    )
    (comp (ref "SJ2")
      (value "SJRND2")
      (footprint "eagle-import:SJ_RND2")
      (libsource (lib "eagle-import") (part "SJRND2"))
    )
    (comp (ref "SJ3")
      (value "SJ-C")
      (footprint "eagle-import:SJW-C")
      (libsource (lib "eagle-import") (part "SJ-C"))
    )
    (comp (ref "SJ4")
      (value "SJRND2")
      (footprint "eagle-import:SJ_RND2")
      (libsource (lib "eagle-import") (part "SJRND2"))
    )
    (comp (ref "SJ5")
      (value "SJRND2")
      (footprint "eagle-import:SJ_RND2")
      (libsource (lib "eagle-import") (part "SJRND2"))
    )
    (comp (ref "SJ6")
      (value "SJRND2")
      (footprint "eagle-import:SJ_RND2")
      (libsource (lib "eagle-import") (part "SJRND2"))
    )
    (comp (ref "SJ7")
      (value "SJRND2")
      (footprint "eagle-import:SJ_RND2")
      (libsource (lib "eagle-import") (part "SJRND2"))
    )
    (comp (ref "SJ8")
      (value "SJRND2")
      (footprint "eagle-import:SJ_RND2")
      (libsource (lib "eagle-import") (part "SJRND2"))
    )
    (comp (ref "SJ9")
      (value "SJRND2")
      (footprint "eagle-import:SJ_RND2")
      (libsource (lib "eagle-import") (part "SJRND2"))
    )
    (comp (ref "SJ10")
      (value "SJRND2")
      (footprint "eagle-import:SJ_RND2")
      (libsource (lib "eagle-import") (part "SJRND2"))
    )
    (comp (ref "SJ11")
      (value "SJ-C")
      (footprint "eagle-import:SJW-C")
      (libsource (lib "eagle-import") (part "SJ-C"))
    )
    (comp (ref "SJ12")
      (value "SJRND2")
      (footprint "eagle-import:SJ_RND2")
      (libsource (lib "eagle-import") (part "SJRND2"))
    )
    (comp (ref "SJ13")
      (value "SJRND2")
      (footprint "eagle-import:SJ_RND2")
      (libsource (lib "eagle-import") (part "SJRND2"))
    )
    (comp (ref "SJ14")
      (value "SJRND2")
      (footprint "eagle-import:SJ_RND2")
      (libsource (lib "eagle-import") (part "SJRND2"))
    )
    (comp (ref "SJ15")
      (value "SJRND2")
      (footprint "eagle-import:SJ_RND2")
      (libsource (lib "eagle-import") (part "SJRND2"))
    )
    (comp (ref "SJ16")
      (value "SJRND2")
      (footprint "eagle-import:SJ_RND2")
      (libsource (lib "eagle-import") (part "SJRND2"))
    )
    (comp (ref "SJ17")
      (value "SJRND2")
      (footprint "eagle-import:SJ_RND2")
      (libsource (lib "eagle-import") (part "SJRND2"))
    )
    (comp (ref "SJ18")
      (value "SJ-C")
      (footprint "eagle-import:SJW-C")
      (libsource (lib "eagle-import") (part "SJ-C"))
    )
    (comp (ref "SJ19")
      (value "SJRND2")
      (footprint "eagle-import:SJ_RND2")
      (libsource (lib "eagle-import") (part "SJRND2"))
    )
    (comp (ref "SJ20")
      (value "SJRND2")
      (footprint "eagle-import:SJ_RND2")
      (libsource (lib "eagle-import") (part "SJRND2"))
    )
    (comp (ref "U1")
      (value "CAN-TXR-PDIP")
      (footprint "eagle-import:DIL08")
      (libsource (lib "eagle-import") (part "PCA82C250"))
    )
    (comp (ref "U2")
      (value "AP1509-50")
      (footprint "eagle-import:SO-08")
      (libsource (lib "eagle-import") (part "AP1509"))
    )
    (comp (ref "U3")
      (value "74HC166")
      (footprint "eagle-import:DIL16")
      (libsource (lib "eagle-import") (part "74166N"))
    )
    (comp (ref "U4")
      (value "74HC166")
      (footprint "eagle-import:DIL16")
      (libsource (lib "eagle-import") (part "74166N"))
    )
    (comp (ref "U5")
      (value "TC4426/28")
      (footprint "eagle-import:DIL08-LONG")
      (libsource (lib "eagle-import") (part "TC4426APDIP"))
    )
    (comp (ref "U6")
      (value "LM324N")
      (footprint "eagle-import:DIL14")
      (libsource (lib "eagle-import") (part "LM324N"))
    )
    (comp (ref "U7")
      (value "TC4426/28")
      (footprint "eagle-import:DIL08-LONG")
      (libsource (lib "eagle-import") (part "TC4426APDIP"))
    )
    (comp (ref "U8")
      (value "TC4426/28")
      (footprint "eagle-import:DIL08-LONG")
      (libsource (lib "eagle-import") (part "TC4426APDIP"))
    )
    (comp (ref "U9")
      (value "LM324N")
      (footprint "eagle-import:DIL14")
      (libsource (lib "eagle-import") (part "LM324N"))
    )
    (comp (ref "U10")
      (value "TC4426/28")
      (footprint "eagle-import:DIL08-LONG")
      (libsource (lib "eagle-import") (part "TC4426APDIP"))
    )
    (comp (ref "U11")
      (value "74AHCT595N")
      (footprint "eagle-import:DIL16")
      (libsource (lib "eagle-import") (part "74595NHCT"))
    )
    (comp (ref "U12")
      (value "ULN2803A")
      (footprint "eagle-import:DIL18-THIN")
      (libsource (lib "eagle-import") (part "ULN2803A"))
    )
    (comp (ref "U13")
      (value "74AHCT595N")
      (footprint "eagle-import:DIL16")
      (libsource (lib "eagle-import") (part "74595NHCT"))
    )
    (comp (ref "U14")
      (value "ULN2803A")
      (footprint "eagle-import:DIL18-THIN")
      (libsource (lib "eagle-import") (part "ULN2803A"))
    )
    (comp (ref "X1")
      (value "RJ45-JACK")
      (footprint "eagle-import:RJ45-PULSE-E5J88")
      (libsource (lib "eagle-import") (part "RJ45-JACKRJ45-PULSE-E5J00"))
    )
    (comp (ref "X2")
      (value "RJ45-JACK")
      (footprint "eagle-import:RJ45-PULSE-E5J88")
      (libsource (lib "eagle-import") (part "RJ45-JACKRJ45-PULSE-E5J00"))
    )
    (comp (ref "X3")
      (value "M08-SCREW")
      (footprint "eagle-import:1X08_TERMINAL")
      (libsource (lib "eagle-import") (part "M08-SCREW"))
    )
    (comp (ref "X4")
      (value "M08-SCREW")
      (footprint "eagle-import:1X08_TERMINAL")
      (libsource (lib "eagle-import") (part "M08-SCREW"))
    )
    (comp (ref "X5")
      (value "CONNECTOR-M023.5MM-LOCK")
      (footprint "eagle-import:SCREWTERMINAL-3.5MM-2_LOCK")
      (libsource (lib "eagle-import") (part "CONNECTOR-M023.5MM-LOCK"))
    )
    (comp (ref "X6")
      (value "M08-SCREW")
      (footprint "eagle-import:1X08_TERMINAL")
      (libsource (lib "eagle-import") (part "M08-SCREW"))
    )
    (comp (ref "X7")
      (value "PORTD")
      (footprint "eagle-import:1X09_TERMINAL")
      (libsource (lib "eagle-import") (part "M09-SCREW"))
    )
    (comp (ref "X8")
      (value "PORTE")
      (footprint "eagle-import:1X09_TERMINAL")
      (libsource (lib "eagle-import") (part "M09-SCREW"))
    )
  )
  (nets
    (net (code "1") (name "+3V3") (class "Default")
      (node (ref "C4") (pin "1") (pinfunction "1_1") (pintype "passive"))
      (node (ref "C8") (pin "1") (pinfunction "1_1") (pintype "passive"))
      (node (ref "G1") (pin "3V3") (pinfunction "3V3_3V3") (pintype "power_in"))
      (node (ref "R26") (pin "1") (pinfunction "1_1") (pintype "passive"))
      (node (ref "R27") (pin "1") (pinfunction "1_1") (pintype "passive"))
      (node (ref "R28") (pin "1") (pinfunction "1_1") (pintype "passive"))
      (node (ref "R29") (pin "1") (pinfunction "1_1") (pintype "passive"))
      (node (ref "R30") (pin "1") (pinfunction "1_1") (pintype "passive"))
      (node (ref "R31") (pin "1") (pinfunction "1_1") (pintype "passive"))
      (node (ref "R32") (pin "1") (pinfunction "1_1") (pintype "passive"))
      (node (ref "R33") (pin "1") (pinfunction "1_1") (pintype "passive"))
      (node (ref "R42") (pin "1") (pinfunction "1_1") (pintype "passive"))
      (node (ref "R43") (pin "1") (pinfunction "1_1") (pintype "passive"))
      (node (ref "R44") (pin "1") (pinfunction "1_1") (pintype "passive"))
      (node (ref "R45") (pin "1") (pinfunction "1_1") (pintype "passive"))
      (node (ref "R46") (pin "1") (pinfunction "1_1") (pintype "passive"))
      (node (ref "R47") (pin "1") (pinfunction "1_1") (pintype "passive"))
      (node (ref "R48") (pin "1") (pinfunction "1_1") (pintype "passive"))
      (node (ref "R49") (pin "1") (pinfunction "1_1") (pintype "passive"))
      (node (ref "R50") (pin "2") (pinfunction "2_2") (pintype "passive"))
      (node (ref "RN1") (pin "1") (pinfunction "1_1") (pintype "passive"))
      (node (ref "RN3") (pin "1") (pinfunction "1_1") (pintype "passive"))
      (node (ref "SJ5") (pin "P$1") (pinfunction "1_P$1") (pintype "passive"))
      (node (ref "U3") (pin "16") (pinfunction "VCC_16") (pintype "power_in"))
      (node (ref "U3") (pin "9") (pinfunction "CLR_9") (pintype "input"))
      (node (ref "U4") (pin "1") (pinfunction "SER_1") (pintype "input"))
      (node (ref "U4") (pin "16") (pinfunction "VCC_16") (pintype "power_in"))
      (node (ref "U4") (pin "9") (pinfunction "CLR_9") (pintype "input"))
    )
    (net (code "2") (name "+5V") (class "Default")
      (node (ref "C1") (pin "1") (pinfunction "1_1") (pintype "passive"))
      (node (ref "C11") (pin "1") (pinfunction "1_1") (pintype "passive"))
      (node (ref "C2") (pin "1") (pinfunction "1_1") (pintype "passive"))
      (node (ref "C3") (pin "1") (pinfunction "1_1") (pintype "passive"))
      (node (ref "G1") (pin "5V2") (pinfunction "5V2_5V2") (pintype "power_in"))
      (node (ref "IC2") (pin "3") (pinfunction "VDD_3") (pintype "power_in"))
      (node (ref "JP1") (pin "3") (pinfunction "3_3") (pintype "passive"))
      (node (ref "JP1") (pin "4") (pinfunction "4_4") (pintype "passive"))
      (node (ref "JP10") (pin "6") (pinfunction "6_6") (pintype "passive"))
      (node (ref "JP2") (pin "3") (pinfunction "3_3") (pintype "passive"))
      (node (ref "JP2") (pin "4") (pinfunction "4_4") (pintype "passive"))
      (node (ref "JP3") (pin "3") (pinfunction "3_3") (pintype "passive"))
      (node (ref "JP3") (pin "4") (pinfunction "4_4") (pintype "passive"))
      (node (ref "JP4") (pin "3") (pinfunction "3_3") (pintype "passive"))
      (node (ref "JP4") (pin "4") (pinfunction "4_4") (pintype "passive"))
      (node (ref "JP5") (pin "6") (pinfunction "6_6") (pintype "passive"))
      (node (ref "JP6") (pin "3") (pinfunction "3_3") (pintype "passive"))
      (node (ref "JP8") (pin "6") (pinfunction "6_6") (pintype "passive"))
      (node (ref "JP9") (pin "6") (pinfunction "6_6") (pintype "passive"))
      (node (ref "R1") (pin "1") (pinfunction "1_1") (pintype "passive"))
      (node (ref "R10") (pin "1") (pinfunction "1_1") (pintype "passive"))
      (node (ref "R11") (pin "1") (pinfunction "1_1") (pintype "passive"))
      (node (ref "R12") (pin "1") (pinfunction "1_1") (pintype "passive"))
      (node (ref "R13") (pin "1") (pinfunction "1_1") (pintype "passive"))
      (node (ref "R14") (pin "1") (pinfunction "1_1") (pintype "passive"))
      (node (ref "R15") (pin "1") (pinfunction "1_1") (pintype "passive"))
      (node (ref "R2") (pin "1") (pinfunction "1_1") (pintype "passive"))
      (node (ref "R3") (pin "2") (pinfunction "2_2") (pintype "passive"))
      (node (ref "R4") (pin "2") (pinfunction "2_2") (pintype "passive"))
      (node (ref "R5") (pin "2") (pinfunction "2_2") (pintype "passive"))
      (node (ref "R6") (pin "1") (pinfunction "1_1") (pintype "passive"))
      (node (ref "R7") (pin "1") (pinfunction "1_1") (pintype "passive"))
      (node (ref "R8") (pin "1") (pinfunction "1_1") (pintype "passive"))
      (node (ref "R9") (pin "1") (pinfunction "1_1") (pintype "passive"))
      (node (ref "SJ14") (pin "P$2") (pinfunction "2_P$2") (pintype "passive"))
      (node (ref "SJ15") (pin "P$2") (pinfunction "2_P$2") (pintype "passive"))
      (node (ref "SJ7") (pin "P$2") (pinfunction "2_P$2") (pintype "passive"))
      (node (ref "SJ8") (pin "P$2") (pinfunction "2_P$2") (pintype "passive"))
      (node (ref "U1") (pin "3") (pinfunction "VCC_3") (pintype "power_in"))
      (node (ref "U11") (pin "10") (pinfunction "SCL_10") (pintype "input"))
      (node (ref "U11") (pin "16") (pinfunction "VCC_16") (pintype "power_in"))
      (node (ref "U13") (pin "10") (pinfunction "SCL_10") (pintype "input"))
      (node (ref "U13") (pin "16") (pinfunction "VCC_16") (pintype "power_in"))
      (node (ref "X5") (pin "1") (pinfunction "1_1") (pintype "passive"))
    )
    (net (code "3") (name "+12V") (class "Default")
      (node (ref "C10") (pin "1") (pinfunction "1_1") (pintype "passive"))
      (node (ref "C5") (pin "1") (pinfunction "1_1") (pintype "passive"))
      (node (ref "C9") (pin "1") (pinfunction "1_1") (pintype "passive"))
      (node (ref "IC1") (pin "5") (pinfunction "IN_5") (pintype "input"))
      (node (ref "J1") (pin "1") (pinfunction "1_1") (pintype "passive"))
      (node (ref "JP5") (pin "7") (pinfunction "7_7") (pintype "passive"))
      (node (ref "JP7") (pin "2") (pinfunction "2_2") (pintype "passive"))
      (node (ref "SJ10") (pin "P$2") (pinfunction "2_P$2") (pintype "passive"))
      (node (ref "SJ16") (pin "P$2") (pinfunction "2_P$2") (pintype "passive"))
      (node (ref "SJ17") (pin "P$2") (pinfunction "2_P$2") (pintype "passive"))
      (node (ref "SJ2") (pin "P$2") (pinfunction "2_P$2") (pintype "passive"))
      (node (ref "SJ9") (pin "P$2") (pinfunction "2_P$2") (pintype "passive"))
      (node (ref "U10") (pin "6") (pinfunction "VDD_6") (pintype "power_in"))
      (node (ref "U2") (pin "1") (pinfunction "VIN_1") (pintype "bidirectional"))
      (node (ref "U5") (pin "6") (pinfunction "VDD_6") (pintype "power_in"))
      (node (ref "U6") (pin "4") (pinfunction "V+_4") (pintype "power_in"))
      (node (ref "U7") (pin "6") (pinfunction "VDD_6") (pintype "power_in"))
      (node (ref "U8") (pin "6") (pinfunction "VDD_6") (pintype "power_in"))
      (node (ref "U9") (pin "4") (pinfunction "V+_4") (pintype "power_in"))
    )
    (net (code "4") (name "/AGND") (class "Default")
      (node (ref "G1") (pin "AGND") (pinfunction "AGND_AGND") (pintype "power_in"))
    )
    (net (code "5") (name "/AVDD") (class "Default")
      (node (ref "G1") (pin "AVDD") (pinfunction "AVDD_AVDD") (pintype "power_in"))
    )
    (net (code "6") (name "/CANH") (class "Default")
      (node (ref "IC2") (pin "7") (pinfunction "CANH_7") (pintype "bidirectional"))
      (node (ref "U1") (pin "7") (pinfunction "CANH_7") (pintype "bidirectional"))
      (node (ref "X1") (pin "1") (pinfunction "1_1") (pintype "passive"))
      (node (ref "X2") (pin "1") (pinfunction "1_1") (pintype "passive"))
    )
    (net (code "7") (name "/CANL") (class "Default")
      (node (ref "IC2") (pin "6") (pinfunction "CANL_6") (pintype "bidirectional"))
      (node (ref "U1") (pin "6") (pinfunction "CANL_6") (pintype "bidirectional"))
      (node (ref "X1") (pin "2") (pinfunction "2_2") (pintype "passive"))
      (node (ref "X2") (pin "2") (pinfunction "2_2") (pintype "passive"))
    )
    (net (code "8") (name "/GND4") (class "Default")
      (node (ref "G1") (pin "GND4") (pinfunction "GND4_GND4") (pintype "power_in"))
    )
    (net (code "9") (name "/PWR_POS") (class "Default")
      (node (ref "R17") (pin "2") (pinfunction "2_2") (pintype "passive"))
      (node (ref "X1") (pin "8") (pinfunction "8_8") (pintype "passive"))
      (node (ref "X2") (pin "8") (pinfunction "8_8") (pintype "passive"))
    )
    (net (code "10") (name "/U5V") (class "Default")
      (node (ref "G1") (pin "U5V") (pinfunction "U5V_U5V") (pintype "power_in"))
    )
    (net (code "11") (name "/VBAT") (class "Default")
      (node (ref "G1") (pin "VBAT") (pinfunction "VBAT_VBAT") (pintype "power_in"))
    )
    (net (code "12") (name "/VDD") (class "Default")
      (node (ref "G1") (pin "VDD") (pinfunction "VDD_VDD") (pintype "power_in"))
    )
    (net (code "13") (name "CANRX") (class "Default")
      (node (ref "G1") (pin "PB8") (pinfunction "PB8_PB8") (pintype "bidirectional"))
      (node (ref "IC2") (pin "4") (pinfunction "RXD_4") (pintype "bidirectional"))
      (node (ref "U1") (pin "4") (pinfunction "RXD_4") (pintype "output"))
    )
    (net (code "14") (name "CANTX") (class "Default")
      (node (ref "G1") (pin "PB9") (pinfunction "PB9_PB9") (pintype "bidirectional"))
      (node (ref "IC2") (pin "1") (pinfunction "TXD_1") (pintype "bidirectional"))
      (node (ref "U1") (pin "1") (pinfunction "TXD_1") (pintype "input"))
    )
    (net (code "15") (name "E_CS") (class "Default")
      (node (ref "G1") (pin "PC10") (pinfunction "PC10_PC10") (pintype "bidirectional"))
      (node (ref "JP5") (pin "4") (pinfunction "4_4") (pintype "passive"))
      (node (ref "R1") (pin "2") (pinfunction "2_2") (pintype "passive"))
    )
    (net (code "16") (name "E_LAT") (class "Default")
      (node (ref "G1") (pin "PC11") (pinfunction "PC11_PC11") (pintype "bidirectional"))
      (node (ref "JP5") (pin "5") (pinfunction "5_5") (pintype "passive"))
      (node (ref "R2") (pin "2") (pinfunction "2_2") (pintype "passive"))
    )
    (net (code "17") (name "GND") (class "Default")
      (node (ref "C1") (pin "2") (pinfunction "2_2") (pintype "passive"))
      (node (ref "C10") (pin "2") (pinfunction "2_2") (pintype "passive"))
      (node (ref "C11") (pin "2") (pinfunction "2_2") (pintype "passive"))
      (node (ref "C2") (pin "2") (pinfunction "2_2") (pintype "passive"))
      (node (ref "C3") (pin "2") (pinfunction "2_2") (pintype "passive"))
      (node (ref "C4") (pin "2") (pinfunction "2_2") (pintype "passive"))
      (node (ref "C5") (pin "2") (pinfunction "2_2") (pintype "passive"))
      (node (ref "C6") (pin "-") (pinfunction "-_-") (pintype "passive"))
      (node (ref "C7") (pin "2") (pinfunction "2_2") (pintype "passive"))
      (node (ref "C8") (pin "2") (pinfunction "2_2") (pintype "passive"))
      (node (ref "C9") (pin "2") (pinfunction "2_2") (pintype "passive"))
      (node (ref "D3") (pin "A") (pinfunction "A_A") (pintype "passive"))
      (node (ref "D4") (pin "A") (pinfunction "A_A") (pintype "passive"))
      (node (ref "G1") (pin "GND3") (pinfunction "GND3_GND3") (pintype "power_in"))
      (node (ref "G1") (pin "GND5") (pinfunction "GND5_GND5") (pintype "power_in"))
      (node (ref "G1") (pin "GND6") (pinfunction "GND6_GND6") (pintype "power_in"))
      (node (ref "G1") (pin "GND7") (pinfunction "GND7_GND7") (pintype "power_in"))
      (node (ref "G1") (pin "GND8") (pinfunction "GND8_GND8") (pintype "power_in"))
      (node (ref "IC1") (pin "2") (pinfunction "GNDSIG_2") (pintype "input"))
      (node (ref "IC1") (pin "3") (pinfunction "~{ON/OFF}_3") (pintype "input"))
      (node (ref "IC1") (pin "4") (pinfunction "GND_4") (pintype "power_in"))
      (node (ref "IC2") (pin "2") (pinfunction "VSS_2") (pintype "power_in"))
      (node (ref "J1") (pin "2") (pinfunction "2_2") (pintype "passive"))
      (node (ref "J1") (pin "3") (pinfunction "3_3") (pintype "passive"))
      (node (ref "JP1") (pin "5") (pinfunction "5_5") (pintype "passive"))
      (node (ref "JP1") (pin "6") (pinfunction "6_6") (pintype "passive"))
      (node (ref "JP10") (pin "5") (pinfunction "5_5") (pintype "passive"))
      (node (ref "JP2") (pin "5") (pinfunction "5_5") (pintype "passive"))
      (node (ref "JP2") (pin "6") (pinfunction "6_6") (pintype "passive"))
      (node (ref "JP3") (pin "5") (pinfunction "5_5") (pintype "passive"))
      (node (ref "JP3") (pin "6") (pinfunction "6_6") (pintype "passive"))
      (node (ref "JP4") (pin "5") (pinfunction "5_5") (pintype "passive"))
      (node (ref "JP4") (pin "6") (pinfunction "6_6") (pintype "passive"))
      (node (ref "JP5") (pin "8") (pinfunction "8_8") (pintype "passive"))
      (node (ref "JP6") (pin "4") (pinfunction "4_4") (pintype "passive"))
      (node (ref "JP8") (pin "5") (pinfunction "5_5") (pintype "passive"))
      (node (ref "JP9") (pin "5") (pinfunction "5_5") (pintype "passive"))
      (node (ref "Q1") (pin "2") (pinfunction "S_2") (pintype "passive"))
      (node (ref "Q10") (pin "2") (pinfunction "S_2") (pintype "passive"))
      (node (ref "Q11") (pin "2") (pinfunction "S_2") (pintype "passive"))
      (node (ref "Q12") (pin "2") (pinfunction "S_2") (pintype "passive"))
      (node (ref "Q13") (pin "2") (pinfunction "S_2") (pintype "passive"))
      (node (ref "Q14") (pin "2") (pinfunction "S_2") (pintype "passive"))
      (node (ref "Q15") (pin "2") (pinfunction "S_2") (pintype "passive"))
      (node (ref "Q16") (pin "2") (pinfunction "S_2") (pintype "passive"))
      (node (ref "Q2") (pin "2") (pinfunction "S_2") (pintype "passive"))
      (node (ref "Q3") (pin "2") (pinfunction "S_2") (pintype "passive"))
      (node (ref "Q4") (pin "2") (pinfunction "S_2") (pintype "passive"))
      (node (ref "Q5") (pin "2") (pinfunction "S_2") (pintype "passive"))
      (node (ref "Q6") (pin "2") (pinfunction "S_2") (pintype "passive"))
      (node (ref "Q7") (pin "2") (pinfunction "S_2") (pintype "passive"))
      (node (ref "Q8") (pin "2") (pinfunction "S_2") (pintype "passive"))
      (node (ref "Q9") (pin "2") (pinfunction "S_2") (pintype "passive"))
      (node (ref "R16") (pin "2") (pinfunction "2_2") (pintype "passive"))
      (node (ref "R51") (pin "1") (pinfunction "1_1") (pintype "passive"))
      (node (ref "SJ11") (pin "2") (pinfunction "2_2") (pintype "passive"))
      (node (ref "SJ12") (pin "P$2") (pinfunction "2_P$2") (pintype "passive"))
      (node (ref "SJ18") (pin "2") (pinfunction "2_2") (pintype "passive"))
      (node (ref "SJ19") (pin "P$2") (pinfunction "2_P$2") (pintype "passive"))
      (node (ref "U1") (pin "2") (pinfunction "GND_2") (pintype "power_in"))
      (node (ref "U10") (pin "3") (pinfunction "VSS_3") (pintype "power_in"))
      (node (ref "U11") (pin "13") (pinfunction "G_13") (pintype "input"))
      (node (ref "U11") (pin "8") (pinfunction "GND_8") (pintype "power_in"))
      (node (ref "U13") (pin "13") (pinfunction "G_13") (pintype "input"))
      (node (ref "U13") (pin "8") (pinfunction "GND_8") (pintype "power_in"))
      (node (ref "U2") (pin "4") (pinfunction "SD_4") (pintype "bidirectional"))
      (node (ref "U2") (pin "5") (pinfunction "GND1_5") (pintype "power_in"))
      (node (ref "U2") (pin "6") (pinfunction "GND2_6") (pintype "power_in"))
      (node (ref "U2") (pin "7") (pinfunction "GND3_7") (pintype "power_in"))
      (node (ref "U2") (pin "8") (pinfunction "GND4_8") (pintype "power_in"))
      (node (ref "U3") (pin "6") (pinfunction "INH_6") (pintype "input"))
      (node (ref "U3") (pin "8") (pinfunction "GND_8") (pintype "power_in"))
      (node (ref "U4") (pin "6") (pinfunction "INH_6") (pintype "input"))
      (node (ref "U4") (pin "8") (pinfunction "GND_8") (pintype "power_in"))
      (node (ref "U5") (pin "3") (pinfunction "VSS_3") (pintype "power_in"))
      (node (ref "U6") (pin "11") (pinfunction "V-_11") (pintype "power_in"))
      (node (ref "U7") (pin "3") (pinfunction "VSS_3") (pintype "power_in"))
      (node (ref "U8") (pin "3") (pinfunction "VSS_3") (pintype "power_in"))
      (node (ref "U9") (pin "11") (pinfunction "V-_11") (pintype "power_in"))
      (node (ref "X1") (pin "3") (pinfunction "3_3") (pintype "passive"))
      (node (ref "X1") (pin "6") (pinfunction "6_6") (pintype "passive"))
      (node (ref "X1") (pin "7") (pinfunction "7_7") (pintype "passive"))
      (node (ref "X2") (pin "3") (pinfunction "3_3") (pintype "passive"))
      (node (ref "X2") (pin "6") (pinfunction "6_6") (pintype "passive"))
      (node (ref "X2") (pin "7") (pinfunction "7_7") (pintype "passive"))
      (node (ref "X5") (pin "2") (pinfunction "2_2") (pintype "passive"))
    )
    (net (code "18") (name "I2CSCL") (class "Default")
      (node (ref "G1") (pin "PB6") (pinfunction "PB6_PB6") (pintype "bidirectional"))
      (node (ref "JP6") (pin "1") (pinfunction "1_1") (pintype "passive"))
      (node (ref "R15") (pin "2") (pinfunction "2_2") (pintype "passive"))
    )
    (net (code "19") (name "I2CSDA") (class "Default")
      (node (ref "G1") (pin "PB7") (pinfunction "PB7_PB7") (pintype "bidirectional"))
      (node (ref "JP6") (pin "2") (pinfunction "2_2") (pintype "passive"))
      (node (ref "R14") (pin "2") (pinfunction "2_2") (pintype "passive"))
    )
    (net (code "20") (name "ILAT") (class "Default")
      (node (ref "G1") (pin "PA6") (pinfunction "PA6_PA6") (pintype "bidirectional"))
      (node (ref "U3") (pin "15") (pinfunction "SH/~{LD}_15") (pintype "input"))
      (node (ref "U4") (pin "15") (pinfunction "SH/~{LD}_15") (pintype "input"))
    )
    (net (code "21") (name "MISO") (class "Default")
      (node (ref "G1") (pin "PB4") (pinfunction "PB4_PB4") (pintype "bidirectional"))
      (node (ref "JP5") (pin "1") (pinfunction "1_1") (pintype "passive"))
    )
    (net (code "22") (name "MISO2") (class "Default")
      (node (ref "G1") (pin "PC2") (pinfunction "PC2_PC2") (pintype "bidirectional"))
      (node (ref "SJ1") (pin "P$2") (pinfunction "2_P$2") (pintype "passive"))
      (node (ref "SJ6") (pin "P$2") (pinfunction "2_P$2") (pintype "passive"))
      (node (ref "U3") (pin "13") (pinfunction "QH_13") (pintype "output"))
    )
    (net (code "23") (name "MOSI") (class "Default")
      (node (ref "G1") (pin "PB5") (pinfunction "PB5_PB5") (pintype "bidirectional"))
      (node (ref "R4") (pin "1") (pinfunction "1_1") (pintype "passive"))
      (node (ref "SJ13") (pin "P$2") (pinfunction "2_P$2") (pintype "passive"))
      (node (ref "SJ3") (pin "1") (pinfunction "1_1") (pintype "passive"))
      (node (ref "U13") (pin "14") (pinfunction "SER_14") (pintype "input"))
    )
    (net (code "24") (name "Net-(D1-PadA)") (class "Default")
      (node (ref "D1") (pin "A") (pinfunction "A_A") (pintype "passive"))
      (node (ref "D2") (pin "A") (pinfunction "A_A") (pintype "passive"))
      (node (ref "JP7") (pin "4") (pinfunction "4_4") (pintype "passive"))
    )
    (net (code "25") (name "Net-(D1-PadC)") (class "Default")
      (node (ref "D1") (pin "C") (pinfunction "C_C") (pintype "passive"))
      (node (ref "D2") (pin "C") (pinfunction "C_C") (pintype "passive"))
      (node (ref "JP7") (pin "1") (pinfunction "1_1") (pintype "passive"))
    )
    (net (code "26") (name "Net-(IC1-OUT)") (class "Default")
      (node (ref "D3") (pin "C") (pinfunction "C_C") (pintype "passive"))
      (node (ref "D4") (pin "C") (pinfunction "C_C") (pintype "passive"))
      (node (ref "IC1") (pin "7") (pinfunction "OUT_7") (pintype "passive"))
      (node (ref "L1") (pin "2") (pinfunction "2_2") (pintype "passive"))
      (node (ref "U2") (pin "2") (pinfunction "VOUT_2") (pintype "bidirectional"))
    )
    (net (code "27") (name "Net-(IC2-RS)") (class "Default")
      (node (ref "IC2") (pin "8") (pinfunction "RS_8") (pintype "bidirectional"))
      (node (ref "R16") (pin "1") (pinfunction "1_1") (pintype "passive"))
      (node (ref "U1") (pin "8") (pinfunction "RS_8") (pintype "input"))
    )
    (net (code "28") (name "Net-(IC2-VREF)") (class "Default")
      (node (ref "IC2") (pin "5") (pinfunction "VREF_5") (pintype "bidirectional"))
      (node (ref "SJ5") (pin "P$2") (pinfunction "2_P$2") (pintype "passive"))
      (node (ref "U1") (pin "5") (pinfunction "VREF_5") (pintype "output"))
    )
    (net (code "29") (name "Net-(JP7-Pad3)") (class "Default")
      (node (ref "JP7") (pin "3") (pinfunction "3_3") (pintype "passive"))
      (node (ref "R17") (pin "1") (pinfunction "1_1") (pintype "passive"))
    )
    (net (code "30") (name "Net-(JP8-Pad1)") (class "Default")
      (node (ref "JP8") (pin "1") (pinfunction "1_1") (pintype "passive"))
      (node (ref "R25") (pin "2") (pinfunction "2_2") (pintype "passive"))
      (node (ref "R26") (pin "2") (pinfunction "2_2") (pintype "passive"))
      (node (ref "RN1") (pin "9") (pinfunction "9_9") (pintype "passive"))
      (node (ref "RN2") (pin "1") (pinfunction "1_1") (pintype "passive"))
      (node (ref "X3") (pin "1") (pinfunction "1_1") (pintype "passive"))
    )
    (net (code "31") (name "Net-(JP9-Pad1)") (class "Default")
      (node (ref "JP9") (pin "1") (pinfunction "1_1") (pintype "passive"))
      (node (ref "R41") (pin "2") (pinfunction "2_2") (pintype "passive"))
      (node (ref "R42") (pin "2") (pinfunction "2_2") (pintype "passive"))
      (node (ref "RN3") (pin "9") (pinfunction "9_9") (pintype "passive"))
      (node (ref "RN4") (pin "1") (pinfunction "1_1") (pintype "passive"))
      (node (ref "X4") (pin "1") (pinfunction "1_1") (pintype "passive"))
    )
    (net (code "32") (name "Net-(Q1-D)") (class "Default")
      (node (ref "Q1") (pin "3") (pinfunction "D_3") (pintype "passive"))
      (node (ref "U12") (pin "11") (pinfunction "O8_11") (pintype "open_collector"))
      (node (ref "X7") (pin "8") (pinfunction "8_8") (pintype "passive"))
    )
    (net (code "33") (name "Net-(Q1-G)") (class "Default")
      (node (ref "Q1") (pin "1") (pinfunction "G_1") (pintype "passive"))
      (node (ref "R52") (pin "2") (pinfunction "2_2") (pintype "passive"))
    )
    (net (code "34") (name "Net-(Q2-D)") (class "Default")
      (node (ref "Q2") (pin "3") (pinfunction "D_3") (pintype "passive"))
      (node (ref "U12") (pin "12") (pinfunction "O7_12") (pintype "open_collector"))
      (node (ref "X7") (pin "7") (pinfunction "7_7") (pintype "passive"))
    )
    (net (code "35") (name "Net-(Q2-G)") (class "Default")
      (node (ref "Q2") (pin "1") (pinfunction "G_1") (pintype "passive"))
      (node (ref "R53") (pin "2") (pinfunction "2_2") (pintype "passive"))
    )
    (net (code "36") (name "Net-(Q3-D)") (class "Default")
      (node (ref "Q3") (pin "3") (pinfunction "D_3") (pintype "passive"))
      (node (ref "U12") (pin "13") (pinfunction "O6_13") (pintype "open_collector"))
      (node (ref "X7") (pin "6") (pinfunction "6_6") (pintype "passive"))
    )
    (net (code "37") (name "Net-(Q3-G)") (class "Default")
      (node (ref "Q3") (pin "1") (pinfunction "G_1") (pintype "passive"))
      (node (ref "R54") (pin "2") (pinfunction "2_2") (pintype "passive"))
    )
    (net (code "38") (name "Net-(Q4-D)") (class "Default")
      (node (ref "Q4") (pin "3") (pinfunction "D_3") (pintype "passive"))
      (node (ref "U12") (pin "14") (pinfunction "O5_14") (pintype "open_collector"))
      (node (ref "X7") (pin "5") (pinfunction "5_5") (pintype "passive"))
    )
    (net (code "39") (name "Net-(Q4-G)") (class "Default")
      (node (ref "Q4") (pin "1") (pinfunction "G_1") (pintype "passive"))
      (node (ref "R55") (pin "2") (pinfunction "2_2") (pintype "passive"))
    )
    (net (code "40") (name "Net-(Q5-D)") (class "Default")
      (node (ref "Q5") (pin "3") (pinfunction "D_3") (pintype "passive"))
      (node (ref "U12") (pin "15") (pinfunction "O4_15") (pintype "open_collector"))
      (node (ref "X7") (pin "4") (pinfunction "4_4") (pintype "passive"))
    )
    (net (code "41") (name "Net-(Q5-G)") (class "Default")
      (node (ref "Q5") (pin "1") (pinfunction "G_1") (pintype "passive"))
      (node (ref "R56") (pin "2") (pinfunction "2_2") (pintype "passive"))
    )
    (net (code "42") (name "Net-(Q6-D)") (class "Default")
      (node (ref "Q6") (pin "3") (pinfunction "D_3") (pintype "passive"))
      (node (ref "U12") (pin "16") (pinfunction "O3_16") (pintype "open_collector"))
      (node (ref "X7") (pin "3") (pinfunction "3_3") (pintype "passive"))
    )
    (net (code "43") (name "Net-(Q6-G)") (class "Default")
      (node (ref "Q6") (pin "1") (pinfunction "G_1") (pintype "passive"))
      (node (ref "R57") (pin "2") (pinfunction "2_2") (pintype "passive"))
    )
    (net (code "44") (name "Net-(Q7-D)") (class "Default")
      (node (ref "Q7") (pin "3") (pinfunction "D_3") (pintype "passive"))
      (node (ref "U12") (pin "17") (pinfunction "O2_17") (pintype "open_collector"))
      (node (ref "X7") (pin "2") (pinfunction "2_2") (pintype "passive"))
    )
    (net (code "45") (name "Net-(Q7-G)") (class "Default")
      (node (ref "Q7") (pin "1") (pinfunction "G_1") (pintype "passive"))
      (node (ref "R58") (pin "2") (pinfunction "2_2") (pintype "passive"))
    )
    (net (code "46") (name "Net-(Q8-D)") (class "Default")
      (node (ref "Q8") (pin "3") (pinfunction "D_3") (pintype "passive"))
      (node (ref "U12") (pin "18") (pinfunction "O1_18") (pintype "open_collector"))
      (node (ref "X7") (pin "1") (pinfunction "1_1") (pintype "passive"))
    )
    (net (code "47") (name "Net-(Q8-G)") (class "Default")
      (node (ref "Q8") (pin "1") (pinfunction "G_1") (pintype "passive"))
      (node (ref "R59") (pin "2") (pinfunction "2_2") (pintype "passive"))
    )
    (net (code "48") (name "Net-(Q9-D)") (class "Default")
      (node (ref "Q9") (pin "3") (pinfunction "D_3") (pintype "passive"))
      (node (ref "U14") (pin "11") (pinfunction "O8_11") (pintype "open_collector"))
      (node (ref "X8") (pin "8") (pinfunction "8_8") (pintype "passive"))
    )
    (net (code "49") (name "Net-(Q9-G)") (class "Default")
      (node (ref "Q9") (pin "1") (pinfunction "G_1") (pintype "passive"))
      (node (ref "R60") (pin "2") (pinfunction "2_2") (pintype "passive"))
    )
    (net (code "50") (name "Net-(Q10-D)") (class "Default")
      (node (ref "Q10") (pin "3") (pinfunction "D_3") (pintype "passive"))
      (node (ref "U14") (pin "12") (pinfunction "O7_12") (pintype "open_collector"))
      (node (ref "X8") (pin "7") (pinfunction "7_7") (pintype "passive"))
    )
    (net (code "51") (name "Net-(Q10-G)") (class "Default")
      (node (ref "Q10") (pin "1") (pinfunction "G_1") (pintype "passive"))
      (node (ref "R61") (pin "2") (pinfunction "2_2") (pintype "passive"))
    )
    (net (code "52") (name "Net-(Q11-D)") (class "Default")
      (node (ref "Q11") (pin "3") (pinfunction "D_3") (pintype "passive"))
      (node (ref "U14") (pin "13") (pinfunction "O6_13") (pintype "open_collector"))
      (node (ref "X8") (pin "6") (pinfunction "6_6") (pintype "passive"))
    )
    (net (code "53") (name "Net-(Q11-G)") (class "Default")
      (node (ref "Q11") (pin "1") (pinfunction "G_1") (pintype "passive"))
      (node (ref "R62") (pin "2") (pinfunction "2_2") (pintype "passive"))
    )
    (net (code "54") (name "Net-(Q12-D)") (class "Default")
      (node (ref "Q12") (pin "3") (pinfunction "D_3") (pintype "passive"))
      (node (ref "U14") (pin "14") (pinfunction "O5_14") (pintype "open_collector"))
      (node (ref "X8") (pin "5") (pinfunction "5_5") (pintype "passive"))
    )
    (net (code "55") (name "Net-(Q12-G)") (class "Default")
      (node (ref "Q12") (pin "1") (pinfunction "G_1") (pintype "passive"))
      (node (ref "R63") (pin "2") (pinfunction "2_2") (pintype "passive"))
    )
    (net (code "56") (name "Net-(Q13-D)") (class "Default")
      (node (ref "Q13") (pin "3") (pinfunction "D_3") (pintype "passive"))
      (node (ref "U14") (pin "15") (pinfunction "O4_15") (pintype "open_collector"))
      (node (ref "X8") (pin "4") (pinfunction "4_4") (pintype "passive"))
    )
    (net (code "57") (name "Net-(Q13-G)") (class "Default")
      (node (ref "Q13") (pin "1") (pinfunction "G_1") (pintype "passive"))
      (node (ref "R64") (pin "2") (pinfunction "2_2") (pintype "passive"))
    )
    (net (code "58") (name "Net-(Q14-D)") (class "Default")
      (node (ref "Q14") (pin "3") (pinfunction "D_3") (pintype "passive"))
      (node (ref "U14") (pin "16") (pinfunction "O3_16") (pintype "open_collector"))
      (node (ref "X8") (pin "3") (pinfunction "3_3") (pintype "passive"))
    )
    (net (code "59") (name "Net-(Q14-G)") (class "Default")
      (node (ref "Q14") (pin "1") (pinfunction "G_1") (pintype "passive"))
      (node (ref "R65") (pin "2") (pinfunction "2_2") (pintype "passive"))
    )
    (net (code "60") (name "Net-(Q15-D)") (class "Default")
      (node (ref "Q15") (pin "3") (pinfunction "D_3") (pintype "passive"))
      (node (ref "U14") (pin "17") (pinfunction "O2_17") (pintype "open_collector"))
      (node (ref "X8") (pin "2") (pinfunction "2_2") (pintype "passive"))
    )
    (net (code "61") (name "Net-(Q15-G)") (class "Default")
      (node (ref "Q15") (pin "1") (pinfunction "G_1") (pintype "passive"))
      (node (ref "R66") (pin "2") (pinfunction "2_2") (pintype "passive"))
    )
    (net (code "62") (name "Net-(Q16-D)") (class "Default")
      (node (ref "Q16") (pin "3") (pinfunction "D_3") (pintype "passive"))
      (node (ref "U14") (pin "18") (pinfunction "O1_18") (pintype "open_collector"))
      (node (ref "X8") (pin "1") (pinfunction "1_1") (pintype "passive"))
    )
    (net (code "63") (name "Net-(Q16-G)") (class "Default")
      (node (ref "Q16") (pin "1") (pinfunction "G_1") (pintype "passive"))
      (node (ref "R67") (pin "2") (pinfunction "2_2") (pintype "passive"))
    )
    (net (code "64") (name "Net-(RN2A-2)") (class "Default")
      (node (ref "R25") (pin "1") (pinfunction "1_1") (pintype "passive"))
      (node (ref "RN2") (pin "16") (pinfunction "2_16") (pintype "passive"))
      (node (ref "U3") (pin "14") (pinfunction "H_14") (pintype "input"))
    )
    (net (code "65") (name "Net-(RN2B-1)") (class "Default")
      (node (ref "JP8") (pin "2") (pinfunction "2_2") (pintype "passive"))
      (node (ref "R24") (pin "2") (pinfunction "2_2") (pintype "passive"))
      (node (ref "R27") (pin "2") (pinfunction "2_2") (pintype "passive"))
      (node (ref "RN1") (pin "8") (pinfunction "8_8") (pintype "passive"))
      (node (ref "RN2") (pin "2") (pinfunction "1_2") (pintype "passive"))
      (node (ref "X3") (pin "2") (pinfunction "2_2") (pintype "passive"))
    )
    (net (code "66") (name "Net-(RN2B-2)") (class "Default")
      (node (ref "R24") (pin "1") (pinfunction "1_1") (pintype "passive"))
      (node (ref "RN2") (pin "15") (pinfunction "2_15") (pintype "passive"))
      (node (ref "U3") (pin "12") (pinfunction "G_12") (pintype "input"))
    )
    (net (code "67") (name "Net-(RN2C-1)") (class "Default")
      (node (ref "JP8") (pin "3") (pinfunction "3_3") (pintype "passive"))
      (node (ref "R23") (pin "2") (pinfunction "2_2") (pintype "passive"))
      (node (ref "R28") (pin "2") (pinfunction "2_2") (pintype "passive"))
      (node (ref "RN1") (pin "7") (pinfunction "7_7") (pintype "passive"))
      (node (ref "RN2") (pin "3") (pinfunction "1_3") (pintype "passive"))
      (node (ref "X3") (pin "3") (pinfunction "3_3") (pintype "passive"))
    )
    (net (code "68") (name "Net-(RN2C-2)") (class "Default")
      (node (ref "R23") (pin "1") (pinfunction "1_1") (pintype "passive"))
      (node (ref "RN2") (pin "14") (pinfunction "2_14") (pintype "passive"))
      (node (ref "U3") (pin "11") (pinfunction "F_11") (pintype "input"))
    )
    (net (code "69") (name "Net-(RN2D-1)") (class "Default")
      (node (ref "JP8") (pin "4") (pinfunction "4_4") (pintype "passive"))
      (node (ref "R22") (pin "2") (pinfunction "2_2") (pintype "passive"))
      (node (ref "R29") (pin "2") (pinfunction "2_2") (pintype "passive"))
      (node (ref "RN1") (pin "6") (pinfunction "6_6") (pintype "passive"))
      (node (ref "RN2") (pin "4") (pinfunction "1_4") (pintype "passive"))
      (node (ref "X3") (pin "4") (pinfunction "4_4") (pintype "passive"))
    )
    (net (code "70") (name "Net-(RN2D-2)") (class "Default")
      (node (ref "R22") (pin "1") (pinfunction "1_1") (pintype "passive"))
      (node (ref "RN2") (pin "13") (pinfunction "2_13") (pintype "passive"))
      (node (ref "U3") (pin "10") (pinfunction "E_10") (pintype "input"))
    )
    (net (code "71") (name "Net-(RN2E-1)") (class "Default")
      (node (ref "JP8") (pin "7") (pinfunction "7_7") (pintype "passive"))
      (node (ref "R21") (pin "2") (pinfunction "2_2") (pintype "passive"))
      (node (ref "R30") (pin "2") (pinfunction "2_2") (pintype "passive"))
      (node (ref "RN1") (pin "5") (pinfunction "5_5") (pintype "passive"))
      (node (ref "RN2") (pin "5") (pinfunction "1_5") (pintype "passive"))
      (node (ref "X3") (pin "5") (pinfunction "5_5") (pintype "passive"))
    )
    (net (code "72") (name "Net-(RN2E-2)") (class "Default")
      (node (ref "R21") (pin "1") (pinfunction "1_1") (pintype "passive"))
      (node (ref "RN2") (pin "12") (pinfunction "2_12") (pintype "passive"))
      (node (ref "U3") (pin "5") (pinfunction "D_5") (pintype "input"))
    )
    (net (code "73") (name "Net-(RN2F-1)") (class "Default")
      (node (ref "JP8") (pin "8") (pinfunction "8_8") (pintype "passive"))
      (node (ref "R20") (pin "2") (pinfunction "2_2") (pintype "passive"))
      (node (ref "R31") (pin "2") (pinfunction "2_2") (pintype "passive"))
      (node (ref "RN1") (pin "4") (pinfunction "4_4") (pintype "passive"))
      (node (ref "RN2") (pin "6") (pinfunction "1_6") (pintype "passive"))
      (node (ref "X3") (pin "6") (pinfunction "6_6") (pintype "passive"))
    )
    (net (code "74") (name "Net-(RN2F-2)") (class "Default")
      (node (ref "R20") (pin "1") (pinfunction "1_1") (pintype "passive"))
      (node (ref "RN2") (pin "11") (pinfunction "2_11") (pintype "passive"))
      (node (ref "U3") (pin "4") (pinfunction "C_4") (pintype "input"))
    )
    (net (code "75") (name "Net-(RN2G-1)") (class "Default")
      (node (ref "JP8") (pin "9") (pinfunction "9_9") (pintype "passive"))
      (node (ref "R19") (pin "2") (pinfunction "2_2") (pintype "passive"))
      (node (ref "R32") (pin "2") (pinfunction "2_2") (pintype "passive"))
      (node (ref "RN1") (pin "3") (pinfunction "3_3") (pintype "passive"))
      (node (ref "RN2") (pin "7") (pinfunction "1_7") (pintype "passive"))
      (node (ref "X3") (pin "7") (pinfunction "7_7") (pintype "passive"))
    )
    (net (code "76") (name "Net-(RN2G-2)") (class "Default")
      (node (ref "R19") (pin "1") (pinfunction "1_1") (pintype "passive"))
      (node (ref "RN2") (pin "10") (pinfunction "2_10") (pintype "passive"))
      (node (ref "U3") (pin "3") (pinfunction "B_3") (pintype "input"))
    )
    (net (code "77") (name "Net-(RN2H-1)") (class "Default")
      (node (ref "JP8") (pin "10") (pinfunction "10_10") (pintype "passive"))
      (node (ref "R18") (pin "2") (pinfunction "2_2") (pintype "passive"))
      (node (ref "R33") (pin "2") (pinfunction "2_2") (pintype "passive"))
      (node (ref "RN1") (pin "2") (pinfunction "2_2") (pintype "passive"))
      (node (ref "RN2") (pin "8") (pinfunction "1_8") (pintype "passive"))
      (node (ref "X3") (pin "8") (pinfunction "8_8") (pintype "passive"))
    )
    (net (code "78") (name "Net-(RN2H-2)") (class "Default")
      (node (ref "R18") (pin "1") (pinfunction "1_1") (pintype "passive"))
      (node (ref "RN2") (pin "9") (pinfunction "2_9") (pintype "passive"))
      (node (ref "U3") (pin "2") (pinfunction "A_2") (pintype "input"))
    )
    (net (code "79") (name "Net-(RN4A-2)") (class "Default")
      (node (ref "R41") (pin "1") (pinfunction "1_1") (pintype "passive"))
      (node (ref "RN4") (pin "16") (pinfunction "2_16") (pintype "passive"))
      (node (ref "U4") (pin "14") (pinfunction "H_14") (pintype "input"))
    )
    (net (code "80") (name "Net-(RN4B-1)") (class "Default")
      (node (ref "JP9") (pin "2") (pinfunction "2_2") (pintype "passive"))
      (node (ref "R40") (pin "2") (pinfunction "2_2") (pintype "passive"))
      (node (ref "R43") (pin "2") (pinfunction "2_2") (pintype "passive"))
      (node (ref "RN3") (pin "8") (pinfunction "8_8") (pintype "passive"))
      (node (ref "RN4") (pin "2") (pinfunction "1_2") (pintype "passive"))
      (node (ref "X4") (pin "2") (pinfunction "2_2") (pintype "passive"))
    )
    (net (code "81") (name "Net-(RN4B-2)") (class "Default")
      (node (ref "R40") (pin "1") (pinfunction "1_1") (pintype "passive"))
      (node (ref "RN4") (pin "15") (pinfunction "2_15") (pintype "passive"))
      (node (ref "U4") (pin "12") (pinfunction "G_12") (pintype "input"))
    )
    (net (code "82") (name "Net-(RN4C-1)") (class "Default")
      (node (ref "JP9") (pin "3") (pinfunction "3_3") (pintype "passive"))
      (node (ref "R39") (pin "2") (pinfunction "2_2") (pintype "passive"))
      (node (ref "R44") (pin "2") (pinfunction "2_2") (pintype "passive"))
      (node (ref "RN3") (pin "7") (pinfunction "7_7") (pintype "passive"))
      (node (ref "RN4") (pin "3") (pinfunction "1_3") (pintype "passive"))
      (node (ref "X4") (pin "3") (pinfunction "3_3") (pintype "passive"))
    )
    (net (code "83") (name "Net-(RN4C-2)") (class "Default")
      (node (ref "R39") (pin "1") (pinfunction "1_1") (pintype "passive"))
      (node (ref "RN4") (pin "14") (pinfunction "2_14") (pintype "passive"))
      (node (ref "U4") (pin "11") (pinfunction "F_11") (pintype "input"))
    )
    (net (code "84") (name "Net-(RN4D-1)") (class "Default")
      (node (ref "JP9") (pin "4") (pinfunction "4_4") (pintype "passive"))
      (node (ref "R38") (pin "2") (pinfunction "2_2") (pintype "passive"))
      (node (ref "R45") (pin "2") (pinfunction "2_2") (pintype "passive"))
      (node (ref "RN3") (pin "6") (pinfunction "6_6") (pintype "passive"))
      (node (ref "RN4") (pin "4") (pinfunction "1_4") (pintype "passive"))
      (node (ref "X4") (pin "4") (pinfunction "4_4") (pintype "passive"))
    )
    (net (code "85") (name "Net-(RN4D-2)") (class "Default")
      (node (ref "R38") (pin "1") (pinfunction "1_1") (pintype "passive"))
      (node (ref "RN4") (pin "13") (pinfunction "2_13") (pintype "passive"))
      (node (ref "U4") (pin "10") (pinfunction "E_10") (pintype "input"))
    )
    (net (code "86") (name "Net-(RN4E-1)") (class "Default")
      (node (ref "JP9") (pin "7") (pinfunction "7_7") (pintype "passive"))
      (node (ref "R37") (pin "2") (pinfunction "2_2") (pintype "passive"))
      (node (ref "R46") (pin "2") (pinfunction "2_2") (pintype "passive"))
      (node (ref "RN3") (pin "5") (pinfunction "5_5") (pintype "passive"))
      (node (ref "RN4") (pin "5") (pinfunction "1_5") (pintype "passive"))
      (node (ref "X4") (pin "5") (pinfunction "5_5") (pintype "passive"))
    )
    (net (code "87") (name "Net-(RN4E-2)") (class "Default")
      (node (ref "R37") (pin "1") (pinfunction "1_1") (pintype "passive"))
      (node (ref "RN4") (pin "12") (pinfunction "2_12") (pintype "passive"))
      (node (ref "U4") (pin "5") (pinfunction "D_5") (pintype "input"))
    )
    (net (code "88") (name "Net-(RN4F-1)") (class "Default")
      (node (ref "JP9") (pin "8") (pinfunction "8_8") (pintype "passive"))
      (node (ref "R36") (pin "2") (pinfunction "2_2") (pintype "passive"))
      (node (ref "R47") (pin "2") (pinfunction "2_2") (pintype "passive"))
      (node (ref "RN3") (pin "4") (pinfunction "4_4") (pintype "passive"))
      (node (ref "RN4") (pin "6") (pinfunction "1_6") (pintype "passive"))
      (node (ref "X4") (pin "6") (pinfunction "6_6") (pintype "passive"))
    )
    (net (code "89") (name "Net-(RN4F-2)") (class "Default")
      (node (ref "R36") (pin "1") (pinfunction "1_1") (pintype "passive"))
      (node (ref "RN4") (pin "11") (pinfunction "2_11") (pintype "passive"))
      (node (ref "U4") (pin "4") (pinfunction "C_4") (pintype "input"))
    )
    (net (code "90") (name "Net-(RN4G-1)") (class "Default")
      (node (ref "JP9") (pin "9") (pinfunction "9_9") (pintype "passive"))
      (node (ref "R35") (pin "2") (pinfunction "2_2") (pintype "passive"))
      (node (ref "R48") (pin "2") (pinfunction "2_2") (pintype "passive"))
      (node (ref "RN3") (pin "3") (pinfunction "3_3") (pintype "passive"))
      (node (ref "RN4") (pin "7") (pinfunction "1_7") (pintype "passive"))
      (node (ref "X4") (pin "7") (pinfunction "7_7") (pintype "passive"))
    )
    (net (code "91") (name "Net-(RN4G-2)") (class "Default")
      (node (ref "R35") (pin "1") (pinfunction "1_1") (pintype "passive"))
      (node (ref "RN4") (pin "10") (pinfunction "2_10") (pintype "passive"))
      (node (ref "U4") (pin "3") (pinfunction "B_3") (pintype "input"))
    )
    (net (code "92") (name "Net-(RN4H-1)") (class "Default")
      (node (ref "JP9") (pin "10") (pinfunction "10_10") (pintype "passive"))
      (node (ref "R34") (pin "2") (pinfunction "2_2") (pintype "passive"))
      (node (ref "R49") (pin "2") (pinfunction "2_2") (pintype "passive"))
      (node (ref "RN3") (pin "2") (pinfunction "2_2") (pintype "passive"))
      (node (ref "RN4") (pin "8") (pinfunction "1_8") (pintype "passive"))
      (node (ref "X4") (pin "8") (pinfunction "8_8") (pintype "passive"))
    )
    (net (code "93") (name "Net-(RN4H-2)") (class "Default")
      (node (ref "R34") (pin "1") (pinfunction "1_1") (pintype "passive"))
      (node (ref "RN4") (pin "9") (pinfunction "2_9") (pintype "passive"))
      (node (ref "U4") (pin "2") (pinfunction "A_2") (pintype "input"))
    )
    (net (code "94") (name "Net-(SJ1-1)") (class "Default")
      (node (ref "G1") (pin "PB14") (pinfunction "PB14_PB14") (pintype "bidirectional"))
      (node (ref "SJ1") (pin "P$1") (pinfunction "1_P$1") (pintype "passive"))
    )
    (net (code "95") (name "Net-(SJ2-1)") (class "Default")
      (node (ref "G1") (pin "VIN2") (pinfunction "VIN2_VIN2") (pintype "power_in"))
      (node (ref "SJ2") (pin "P$1") (pinfunction "1_P$1") (pintype "passive"))
    )
    (net (code "96") (name "Net-(SJ4-2)") (class "Default")
      (node (ref "JP5") (pin "2") (pinfunction "2_2") (pintype "passive"))
      (node (ref "SJ3") (pin "2") (pinfunction "2_2") (pintype "passive"))
      (node (ref "SJ4") (pin "P$2") (pinfunction "2_P$2") (pintype "passive"))
    )
    (net (code "97") (name "Net-(SJ7-1)") (class "Default")
      (node (ref "SJ11") (pin "1") (pinfunction "1_1") (pintype "passive"))
      (node (ref "SJ7") (pin "P$1") (pinfunction "1_P$1") (pintype "passive"))
      (node (ref "SJ9") (pin "P$1") (pinfunction "1_P$1") (pintype "passive"))
      (node (ref "U12") (pin "9") (pinfunction "GND_9") (pintype "power_in"))
    )
    (net (code "98") (name "Net-(SJ10-1)") (class "Default")
      (node (ref "SJ10") (pin "P$1") (pinfunction "1_P$1") (pintype "passive"))
      (node (ref "SJ12") (pin "P$1") (pinfunction "1_P$1") (pintype "passive"))
      (node (ref "SJ8") (pin "P$1") (pinfunction "1_P$1") (pintype "passive"))
      (node (ref "U12") (pin "10") (pinfunction "CD+_10") (pintype "passive"))
      (node (ref "X7") (pin "9") (pinfunction "9_9") (pintype "passive"))
    )
    (net (code "99") (name "Net-(SJ14-1)") (class "Default")
      (node (ref "SJ14") (pin "P$1") (pinfunction "1_P$1") (pintype "passive"))
      (node (ref "SJ16") (pin "P$1") (pinfunction "1_P$1") (pintype "passive"))
      (node (ref "SJ18") (pin "1") (pinfunction "1_1") (pintype "passive"))
      (node (ref "U14") (pin "9") (pinfunction "GND_9") (pintype "power_in"))
    )
    (net (code "100") (name "Net-(SJ15-1)") (class "Default")
      (node (ref "SJ15") (pin "P$1") (pinfunction "1_P$1") (pintype "passive"))
      (node (ref "SJ17") (pin "P$1") (pinfunction "1_P$1") (pintype "passive"))
      (node (ref "SJ19") (pin "P$1") (pinfunction "1_P$1") (pintype "passive"))
      (node (ref "U14") (pin "10") (pinfunction "CD+_10") (pintype "passive"))
      (node (ref "X8") (pin "9") (pinfunction "9_9") (pintype "passive"))
    )
    (net (code "101") (name "Net-(SJ20-2)") (class "Default")
      (node (ref "G1") (pin "PB13") (pinfunction "PB13_PB13") (pintype "bidirectional"))
      (node (ref "SJ20") (pin "P$2") (pinfunction "2_P$2") (pintype "passive"))
    )
    (net (code "102") (name "Net-(U5A-O)") (class "Default")
      (node (ref "JP10") (pin "1") (pinfunction "1_1") (pintype "passive"))
      (node (ref "U5") (pin "7") (pinfunction "O_7") (pintype "output"))
      (node (ref "U6") (pin "7") (pinfunction "OUT_7") (pintype "output"))
      (node (ref "X6") (pin "1") (pinfunction "1_1") (pintype "passive"))
    )
    (net (code "103") (name "Net-(U5B-O)") (class "Default")
      (node (ref "JP10") (pin "2") (pinfunction "2_2") (pintype "passive"))
      (node (ref "U5") (pin "5") (pinfunction "O_5") (pintype "output"))
      (node (ref "U6") (pin "8") (pinfunction "OUT_8") (pintype "output"))
      (node (ref "X6") (pin "2") (pinfunction "2_2") (pintype "passive"))
    )
    (net (code "104") (name "Net-(U6A--IN)") (class "Default")
      (node (ref "R50") (pin "1") (pinfunction "1_1") (pintype "passive"))
      (node (ref "R51") (pin "2") (pinfunction "2_2") (pintype "passive"))
      (node (ref "U6") (pin "13") (pinfunction "-IN_13") (pintype "input"))
      (node (ref "U6") (pin "2") (pinfunction "-IN_2") (pintype "input"))
      (node (ref "U6") (pin "6") (pinfunction "-IN_6") (pintype "input"))
      (node (ref "U6") (pin "9") (pinfunction "-IN_9") (pintype "input"))
      (node (ref "U9") (pin "13") (pinfunction "-IN_13") (pintype "input"))
      (node (ref "U9") (pin "2") (pinfunction "-IN_2") (pintype "input"))
      (node (ref "U9") (pin "6") (pinfunction "-IN_6") (pintype "input"))
      (node (ref "U9") (pin "9") (pinfunction "-IN_9") (pintype "input"))
    )
    (net (code "105") (name "Net-(U6A-OUT)") (class "Default")
      (node (ref "JP10") (pin "3") (pinfunction "3_3") (pintype "passive"))
      (node (ref "U6") (pin "1") (pinfunction "OUT_1") (pintype "output"))
      (node (ref "U7") (pin "5") (pinfunction "O_5") (pintype "output"))
      (node (ref "X6") (pin "3") (pinfunction "3_3") (pintype "passive"))
    )
    (net (code "106") (name "Net-(U6D-OUT)") (class "Default")
      (node (ref "JP10") (pin "4") (pinfunction "4_4") (pintype "passive"))
      (node (ref "U6") (pin "14") (pinfunction "OUT_14") (pintype "output"))
      (node (ref "U7") (pin "7") (pinfunction "O_7") (pintype "output"))
      (node (ref "X6") (pin "4") (pinfunction "4_4") (pintype "passive"))
    )
    (net (code "107") (name "Net-(U8A-O)") (class "Default")
      (node (ref "JP10") (pin "7") (pinfunction "7_7") (pintype "passive"))
      (node (ref "U8") (pin "7") (pinfunction "O_7") (pintype "output"))
      (node (ref "U9") (pin "7") (pinfunction "OUT_7") (pintype "output"))
      (node (ref "X6") (pin "5") (pinfunction "5_5") (pintype "passive"))
    )
    (net (code "108") (name "Net-(U8B-O)") (class "Default")
      (node (ref "JP10") (pin "8") (pinfunction "8_8") (pintype "passive"))
      (node (ref "U8") (pin "5") (pinfunction "O_5") (pintype "output"))
      (node (ref "U9") (pin "8") (pinfunction "OUT_8") (pintype "output"))
      (node (ref "X6") (pin "6") (pinfunction "6_6") (pintype "passive"))
    )
    (net (code "109") (name "Net-(U10A-O)") (class "Default")
      (node (ref "JP10") (pin "10") (pinfunction "10_10") (pintype "passive"))
      (node (ref "U10") (pin "7") (pinfunction "O_7") (pintype "output"))
      (node (ref "U9") (pin "14") (pinfunction "OUT_14") (pintype "output"))
      (node (ref "X6") (pin "8") (pinfunction "8_8") (pintype "passive"))
    )
    (net (code "110") (name "Net-(U10B-O)") (class "Default")
      (node (ref "JP10") (pin "9") (pinfunction "9_9") (pintype "passive"))
      (node (ref "U10") (pin "5") (pinfunction "O_5") (pintype "output"))
      (node (ref "U9") (pin "1") (pinfunction "OUT_1") (pintype "output"))
      (node (ref "X6") (pin "7") (pinfunction "7_7") (pintype "passive"))
    )
    (net (code "111") (name "Net-(U11A-QA)") (class "Default")
      (node (ref "R59") (pin "1") (pinfunction "1_1") (pintype "passive"))
      (node (ref "U11") (pin "15") (pinfunction "QA_15") (pintype "tri_state"))
      (node (ref "U12") (pin "1") (pinfunction "I1_1") (pintype "input"))
    )
    (net (code "112") (name "Net-(U11A-QB)") (class "Default")
      (node (ref "R58") (pin "1") (pinfunction "1_1") (pintype "passive"))
      (node (ref "U11") (pin "1") (pinfunction "QB_1") (pintype "tri_state"))
      (node (ref "U12") (pin "2") (pinfunction "I2_2") (pintype "input"))
    )
    (net (code "113") (name "Net-(U11A-QC)") (class "Default")
      (node (ref "R57") (pin "1") (pinfunction "1_1") (pintype "passive"))
      (node (ref "U11") (pin "2") (pinfunction "QC_2") (pintype "tri_state"))
      (node (ref "U12") (pin "3") (pinfunction "I3_3") (pintype "input"))
    )
    (net (code "114") (name "Net-(U11A-QD)") (class "Default")
      (node (ref "R56") (pin "1") (pinfunction "1_1") (pintype "passive"))
      (node (ref "U11") (pin "3") (pinfunction "QD_3") (pintype "tri_state"))
      (node (ref "U12") (pin "4") (pinfunction "I4_4") (pintype "input"))
    )
    (net (code "115") (name "Net-(U11A-QE)") (class "Default")
      (node (ref "R55") (pin "1") (pinfunction "1_1") (pintype "passive"))
      (node (ref "U11") (pin "4") (pinfunction "QE_4") (pintype "tri_state"))
      (node (ref "U12") (pin "5") (pinfunction "I5_5") (pintype "input"))
    )
    (net (code "116") (name "Net-(U11A-QF)") (class "Default")
      (node (ref "R54") (pin "1") (pinfunction "1_1") (pintype "passive"))
      (node (ref "U11") (pin "5") (pinfunction "QF_5") (pintype "tri_state"))
      (node (ref "U12") (pin "6") (pinfunction "I6_6") (pintype "input"))
    )
    (net (code "117") (name "Net-(U11A-QG)") (class "Default")
      (node (ref "R53") (pin "1") (pinfunction "1_1") (pintype "passive"))
      (node (ref "U11") (pin "6") (pinfunction "QG_6") (pintype "tri_state"))
      (node (ref "U12") (pin "7") (pinfunction "I7_7") (pintype "input"))
    )
    (net (code "118") (name "Net-(U11A-QH)") (class "Default")
      (node (ref "R52") (pin "1") (pinfunction "1_1") (pintype "passive"))
      (node (ref "U11") (pin "7") (pinfunction "QH_7") (pintype "tri_state"))
      (node (ref "U12") (pin "8") (pinfunction "I8_8") (pintype "input"))
    )
    (net (code "119") (name "Net-(U13A-QA)") (class "Default")
      (node (ref "R67") (pin "1") (pinfunction "1_1") (pintype "passive"))
      (node (ref "U13") (pin "15") (pinfunction "QA_15") (pintype "tri_state"))
      (node (ref "U14") (pin "1") (pinfunction "I1_1") (pintype "input"))
    )
    (net (code "120") (name "Net-(U13A-QB)") (class "Default")
      (node (ref "R66") (pin "1") (pinfunction "1_1") (pintype "passive"))
      (node (ref "U13") (pin "1") (pinfunction "QB_1") (pintype "tri_state"))
      (node (ref "U14") (pin "2") (pinfunction "I2_2") (pintype "input"))
    )
    (net (code "121") (name "Net-(U13A-QC)") (class "Default")
      (node (ref "R65") (pin "1") (pinfunction "1_1") (pintype "passive"))
      (node (ref "U13") (pin "2") (pinfunction "QC_2") (pintype "tri_state"))
      (node (ref "U14") (pin "3") (pinfunction "I3_3") (pintype "input"))
    )
    (net (code "122") (name "Net-(U13A-QD)") (class "Default")
      (node (ref "R64") (pin "1") (pinfunction "1_1") (pintype "passive"))
      (node (ref "U13") (pin "3") (pinfunction "QD_3") (pintype "tri_state"))
      (node (ref "U14") (pin "4") (pinfunction "I4_4") (pintype "input"))
    )
    (net (code "123") (name "Net-(U13A-QE)") (class "Default")
      (node (ref "R63") (pin "1") (pinfunction "1_1") (pintype "passive"))
      (node (ref "U13") (pin "4") (pinfunction "QE_4") (pintype "tri_state"))
      (node (ref "U14") (pin "5") (pinfunction "I5_5") (pintype "input"))
    )
    (net (code "124") (name "Net-(U13A-QF)") (class "Default")
      (node (ref "R62") (pin "1") (pinfunction "1_1") (pintype "passive"))
      (node (ref "U13") (pin "5") (pinfunction "QF_5") (pintype "tri_state"))
      (node (ref "U14") (pin "6") (pinfunction "I6_6") (pintype "input"))
    )
    (net (code "125") (name "Net-(U13A-QG)") (class "Default")
      (node (ref "R61") (pin "1") (pinfunction "1_1") (pintype "passive"))
      (node (ref "U13") (pin "6") (pinfunction "QG_6") (pintype "tri_state"))
      (node (ref "U14") (pin "7") (pinfunction "I7_7") (pintype "input"))
    )
    (net (code "126") (name "Net-(U13A-QH)") (class "Default")
      (node (ref "R60") (pin "1") (pinfunction "1_1") (pintype "passive"))
      (node (ref "U13") (pin "7") (pinfunction "QH_7") (pintype "tri_state"))
      (node (ref "U14") (pin "8") (pinfunction "I8_8") (pintype "input"))
    )
    (net (code "127") (name "Net-(X1-Pad4)") (class "Default")
      (node (ref "X1") (pin "4") (pinfunction "4_4") (pintype "passive"))
      (node (ref "X2") (pin "4") (pinfunction "4_4") (pintype "passive"))
    )
    (net (code "128") (name "Net-(X1-Pad5)") (class "Default")
      (node (ref "X1") (pin "5") (pinfunction "5_5") (pintype "passive"))
      (node (ref "X2") (pin "5") (pinfunction "5_5") (pintype "passive"))
    )
    (net (code "129") (name "OLAT") (class "Default")
      (node (ref "G1") (pin "PA8") (pinfunction "PA8_PA8") (pintype "bidirectional"))
      (node (ref "R3") (pin "1") (pinfunction "1_1") (pintype "passive"))
      (node (ref "U11") (pin "12") (pinfunction "RCK_12") (pintype "input"))
      (node (ref "U13") (pin "12") (pinfunction "RCK_12") (pintype "input"))
    )
    (net (code "130") (name "SCK") (class "Default")
      (node (ref "G1") (pin "PB3") (pinfunction "PB3_PB3") (pintype "bidirectional"))
      (node (ref "JP5") (pin "3") (pinfunction "3_3") (pintype "passive"))
      (node (ref "R5") (pin "1") (pinfunction "1_1") (pintype "passive"))
      (node (ref "U11") (pin "11") (pinfunction "SCK_11") (pintype "input"))
      (node (ref "U13") (pin "11") (pinfunction "SCK_11") (pintype "input"))
    )
    (net (code "131") (name "SCK2") (class "Default")
      (node (ref "G1") (pin "PB10") (pinfunction "PB10_PB10") (pintype "bidirectional"))
      (node (ref "SJ20") (pin "P$1") (pinfunction "1_P$1") (pintype "passive"))
      (node (ref "U3") (pin "7") (pinfunction "CLK_7") (pintype "input"))
      (node (ref "U4") (pin "7") (pinfunction "CLK_7") (pintype "input"))
    )
    (net (code "132") (name "SLNK1") (class "Default")
      (node (ref "SJ13") (pin "P$1") (pinfunction "1_P$1") (pintype "passive"))
      (node (ref "U11") (pin "14") (pinfunction "SER_14") (pintype "input"))
      (node (ref "U13") (pin "9") (pinfunction "QH*_9") (pintype "tri_state"))
    )
    (net (code "133") (name "SLNK2") (class "Default")
      (node (ref "SJ4") (pin "P$1") (pinfunction "1_P$1") (pintype "passive"))
      (node (ref "U11") (pin "9") (pinfunction "QH*_9") (pintype "tri_state"))
    )
    (net (code "134") (name "SLNK3") (class "Default")
      (node (ref "SJ6") (pin "P$1") (pinfunction "1_P$1") (pintype "passive"))
      (node (ref "U3") (pin "1") (pinfunction "SER_1") (pintype "input"))
      (node (ref "U4") (pin "13") (pinfunction "QH_13") (pintype "output"))
    )
    (net (code "135") (name "SRV1") (class "Default")
      (node (ref "G1") (pin "PC9") (pinfunction "PC9_PC9") (pintype "bidirectional"))
      (node (ref "JP4") (pin "2") (pinfunction "2_2") (pintype "passive"))
      (node (ref "R13") (pin "2") (pinfunction "2_2") (pintype "passive"))
    )
    (net (code "136") (name "SRV2") (class "Default")
      (node (ref "G1") (pin "PC7") (pinfunction "PC7_PC7") (pintype "bidirectional"))
      (node (ref "JP4") (pin "1") (pinfunction "1_1") (pintype "passive"))
      (node (ref "R12") (pin "2") (pinfunction "2_2") (pintype "passive"))
    )
    (net (code "137") (name "SRV3") (class "Default")
      (node (ref "G1") (pin "PC8") (pinfunction "PC8_PC8") (pintype "bidirectional"))
      (node (ref "JP3") (pin "2") (pinfunction "2_2") (pintype "passive"))
      (node (ref "R11") (pin "2") (pinfunction "2_2") (pintype "passive"))
    )
    (net (code "138") (name "SRV4") (class "Default")
      (node (ref "G1") (pin "PC6") (pinfunction "PC6_PC6") (pintype "bidirectional"))
      (node (ref "JP3") (pin "1") (pinfunction "1_1") (pintype "passive"))
      (node (ref "R10") (pin "2") (pinfunction "2_2") (pintype "passive"))
    )
    (net (code "139") (name "SRV5") (class "Default")
      (node (ref "G1") (pin "PF1-PH1") (pinfunction "PF1-PH1_PF1-PH1") (pintype "bidirectional"))
      (node (ref "JP2") (pin "2") (pinfunction "2_2") (pintype "passive"))
      (node (ref "R9") (pin "2") (pinfunction "2_2") (pintype "passive"))
    )
    (net (code "140") (name "SRV6") (class "Default")
      (node (ref "G1") (pin "PA15") (pinfunction "PA15_PA15") (pintype "bidirectional"))
      (node (ref "JP2") (pin "1") (pinfunction "1_1") (pintype "passive"))
      (node (ref "R8") (pin "2") (pinfunction "2_2") (pintype "passive"))
    )
    (net (code "141") (name "SRV7") (class "Default")
      (node (ref "G1") (pin "PC12") (pinfunction "PC12_PC12") (pintype "bidirectional"))
      (node (ref "JP1") (pin "2") (pinfunction "2_2") (pintype "passive"))
      (node (ref "R7") (pin "2") (pinfunction "2_2") (pintype "passive"))
    )
    (net (code "142") (name "SRV8") (class "Default")
      (node (ref "G1") (pin "PD2") (pinfunction "PD2_PD2") (pintype "bidirectional"))
      (node (ref "JP1") (pin "1") (pinfunction "1_1") (pintype "passive"))
      (node (ref "R6") (pin "2") (pinfunction "2_2") (pintype "passive"))
    )
    (net (code "143") (name "TDRV1") (class "Default")
      (node (ref "G1") (pin "PB12") (pinfunction "PB12_PB12") (pintype "bidirectional"))
      (node (ref "U10") (pin "2") (pinfunction "I_2") (pintype "input"))
      (node (ref "U9") (pin "12") (pinfunction "+IN_12") (pintype "input"))
    )
    (net (code "144") (name "TDRV2") (class "Default")
      (node (ref "G1") (pin "PB2") (pinfunction "PB2_PB2") (pintype "bidirectional"))
      (node (ref "U10") (pin "4") (pinfunction "I_4") (pintype "input"))
      (node (ref "U9") (pin "3") (pinfunction "+IN_3") (pintype "input"))
    )
    (net (code "145") (name "TDRV3") (class "Default")
      (node (ref "G1") (pin "PB15") (pinfunction "PB15_PB15") (pintype "bidirectional"))
      (node (ref "U8") (pin "4") (pinfunction "I_4") (pintype "input"))
      (node (ref "U9") (pin "10") (pinfunction "+IN_10") (pintype "input"))
    )
    (net (code "146") (name "TDRV4") (class "Default")
      (node (ref "G1") (pin "PB1") (pinfunction "PB1_PB1") (pintype "bidirectional"))
      (node (ref "U8") (pin "2") (pinfunction "I_2") (pintype "input"))
      (node (ref "U9") (pin "5") (pinfunction "+IN_5") (pintype "input"))
    )
    (net (code "147") (name "TDRV5") (class "Default")
      (node (ref "G1") (pin "PA0") (pinfunction "PA0_PA0") (pintype "bidirectional"))
      (node (ref "U6") (pin "12") (pinfunction "+IN_12") (pintype "input"))
      (node (ref "U7") (pin "2") (pinfunction "I_2") (pintype "input"))
    )
    (net (code "148") (name "TDRV6") (class "Default")
      (node (ref "G1") (pin "PA4") (pinfunction "PA4_PA4") (pintype "bidirectional"))
      (node (ref "U6") (pin "3") (pinfunction "+IN_3") (pintype "input"))
      (node (ref "U7") (pin "4") (pinfunction "I_4") (pintype "input"))
    )
    (net (code "149") (name "TDRV7") (class "Default")
      (node (ref "G1") (pin "PC3") (pinfunction "PC3_PC3") (pintype "bidirectional"))
      (node (ref "U5") (pin "4") (pinfunction "I_4") (pintype "input"))
      (node (ref "U6") (pin "10") (pinfunction "+IN_10") (pintype "input"))
    )
    (net (code "150") (name "TDRV8") (class "Default")
      (node (ref "G1") (pin "PC0") (pinfunction "PC0_PC0") (pintype "bidirectional"))
      (node (ref "U5") (pin "2") (pinfunction "I_2") (pintype "input"))
      (node (ref "U6") (pin "5") (pinfunction "+IN_5") (pintype "input"))
    )
    (net (code "151") (name "V+") (class "Default")
      (node (ref "C6") (pin "+") (pinfunction "+_+") (pintype "passive"))
      (node (ref "C7") (pin "1") (pinfunction "1_1") (pintype "passive"))
      (node (ref "G1") (pin "E5V") (pinfunction "E5V_E5V") (pintype "power_in"))
      (node (ref "IC1") (pin "1") (pinfunction "FB_1") (pintype "input"))
      (node (ref "L1") (pin "1") (pinfunction "1_1") (pintype "passive"))
      (node (ref "U2") (pin "3") (pinfunction "FB_3") (pintype "bidirectional"))
    )
    (net (code "152") (name "unconnected-(G1-PadBOOT0)") (class "Default")
      (node (ref "G1") (pin "BOOT0") (pinfunction "BOOT0_BOOT0") (pintype "bidirectional"))
    )
    (net (code "153") (name "unconnected-(G1-PadIOREF2)") (class "Default")
      (node (ref "G1") (pin "IOREF2") (pinfunction "IOREF2_IOREF2") (pintype "input"))
    )
    (net (code "154") (name "unconnected-(G1-PadNC1-PF7)") (class "Default")
      (node (ref "G1") (pin "NC1-PF7") (pinfunction "NC1-PF7_NC1-PF7") (pintype "bidirectional"))
    )
    (net (code "155") (name "unconnected-(G1-PadNC2-PF6)") (class "Default")
      (node (ref "G1") (pin "NC2-PF6") (pinfunction "NC2-PF6_NC2-PF6") (pintype "bidirectional"))
    )
    (net (code "156") (name "unconnected-(G1-PadNC3)") (class "Default")
      (node (ref "G1") (pin "NC3") (pinfunction "NC3_NC3") (pintype "no_connect"))
    )
    (net (code "157") (name "unconnected-(G1-PadNC4)") (class "Default")
      (node (ref "G1") (pin "NC4") (pinfunction "NC4_NC4") (pintype "no_connect"))
    )
    (net (code "158") (name "unconnected-(G1-PadNC5-PD8)") (class "Default")
      (node (ref "G1") (pin "NC5-PD8") (pinfunction "NC5-PD8_NC5-PD8") (pintype "bidirectional"))
    )
    (net (code "159") (name "unconnected-(G1-PadNC6-PB11)") (class "Default")
      (node (ref "G1") (pin "NC6-PB11") (pinfunction "NC6-PB11_NC6-PB11") (pintype "no_connect"))
    )
    (net (code "160") (name "unconnected-(G1-PadNC7-PF5)") (class "Default")
      (node (ref "G1") (pin "NC7-PF5") (pinfunction "NC7-PF5_NC7-PF5") (pintype "bidirectional"))
    )
    (net (code "161") (name "unconnected-(G1-PadNC8-PF4)") (class "Default")
      (node (ref "G1") (pin "NC8-PF4") (pinfunction "NC8-PF4_NC8-PF4") (pintype "bidirectional"))
    )
    (net (code "162") (name "unconnected-(G1-PadNRESET)") (class "Default")
      (node (ref "G1") (pin "NRESET") (pinfunction "NRESET_NRESET") (pintype "input"))
    )
    (net (code "163") (name "unconnected-(G1-PadPA1)") (class "Default")
      (node (ref "G1") (pin "PA1") (pinfunction "PA1_PA1") (pintype "bidirectional"))
    )
    (net (code "164") (name "unconnected-(G1-PadPA2)") (class "Default")
      (node (ref "G1") (pin "PA2") (pinfunction "PA2_PA2") (pintype "bidirectional"))
    )
    (net (code "165") (name "unconnected-(G1-PadPA3)") (class "Default")
      (node (ref "G1") (pin "PA3") (pinfunction "PA3_PA3") (pintype "bidirectional"))
    )
    (net (code "166") (name "unconnected-(G1-PadPA5)") (class "Default")
      (node (ref "G1") (pin "PA5") (pinfunction "PA5_PA5") (pintype "bidirectional"))
    )
    (net (code "167") (name "unconnected-(G1-PadPA7)") (class "Default")
      (node (ref "G1") (pin "PA7") (pinfunction "PA7_PA7") (pintype "bidirectional"))
    )
    (net (code "168") (name "unconnected-(G1-PadPA9)") (class "Default")
      (node (ref "G1") (pin "PA9") (pinfunction "PA9_PA9") (pintype "bidirectional"))
    )
    (net (code "169") (name "unconnected-(G1-PadPA10)") (class "Default")
      (node (ref "G1") (pin "PA10") (pinfunction "PA10_PA10") (pintype "bidirectional"))
    )
    (net (code "170") (name "unconnected-(G1-PadPA11)") (class "Default")
      (node (ref "G1") (pin "PA11") (pinfunction "PA11_PA11") (pintype "bidirectional"))
    )
    (net (code "171") (name "unconnected-(G1-PadPA12)") (class "Default")
      (node (ref "G1") (pin "PA12") (pinfunction "PA12_PA12") (pintype "bidirectional"))
    )
    (net (code "172") (name "unconnected-(G1-PadPA13)") (class "Default")
      (node (ref "G1") (pin "PA13") (pinfunction "PA13_PA13") (pintype "bidirectional"))
    )
    (net (code "173") (name "unconnected-(G1-PadPA14)") (class "Default")
      (node (ref "G1") (pin "PA14") (pinfunction "PA14_PA14") (pintype "bidirectional"))
    )
    (net (code "174") (name "unconnected-(G1-PadPB0)") (class "Default")
      (node (ref "G1") (pin "PB0") (pinfunction "PB0_PB0") (pintype "bidirectional"))
    )
    (net (code "175") (name "unconnected-(G1-PadPC1)") (class "Default")
      (node (ref "G1") (pin "PC1") (pinfunction "PC1_PC1") (pintype "bidirectional"))
    )
    (net (code "176") (name "unconnected-(G1-PadPC4)") (class "Default")
      (node (ref "G1") (pin "PC4") (pinfunction "PC4_PC4") (pintype "bidirectional"))
    )
    (net (code "177") (name "unconnected-(G1-PadPC5)") (class "Default")
      (node (ref "G1") (pin "PC5") (pinfunction "PC5_PC5") (pintype "bidirectional"))
    )
    (net (code "178") (name "unconnected-(G1-PadPC13)") (class "Default")
      (node (ref "G1") (pin "PC13") (pinfunction "PC13_PC13") (pintype "bidirectional"))
    )
    (net (code "179") (name "unconnected-(G1-PadPC14)") (class "Default")
      (node (ref "G1") (pin "PC14") (pinfunction "PC14_PC14") (pintype "bidirectional"))
    )
    (net (code "180") (name "unconnected-(G1-PadPC15)") (class "Default")
      (node (ref "G1") (pin "PC15") (pinfunction "PC15_PC15") (pintype "bidirectional"))
    )
    (net (code "181") (name "unconnected-(G1-PadPF0-PH0)") (class "Default")
      (node (ref "G1") (pin "PF0-PH0") (pinfunction "PF0-PH0_PF0-PH0") (pintype "bidirectional"))
    )
    (net (code "182") (name "unconnected-(H1-MOUNT-PadB3,3)") (class "Default")
      (node (ref "H1") (pin "B3,3") (pinfunction "MOUNT_B3,3") (pintype "passive"))
    )
    (net (code "183") (name "unconnected-(H2-MOUNT-PadB3,3)") (class "Default")
      (node (ref "H2") (pin "B3,3") (pinfunction "MOUNT_B3,3") (pintype "passive"))
    )
    (net (code "184") (name "unconnected-(H3-MOUNT-PadB3,3)") (class "Default")
      (node (ref "H3") (pin "B3,3") (pinfunction "MOUNT_B3,3") (pintype "passive"))
    )
    (net (code "185") (name "unconnected-(H4-MOUNT-PadB3,3)") (class "Default")
      (node (ref "H4") (pin "B3,3") (pinfunction "MOUNT_B3,3") (pintype "passive"))
    )
  )
)
